# DCC-command-center-V2.net
KiCad netlist of a schematic drawn in EAGLE
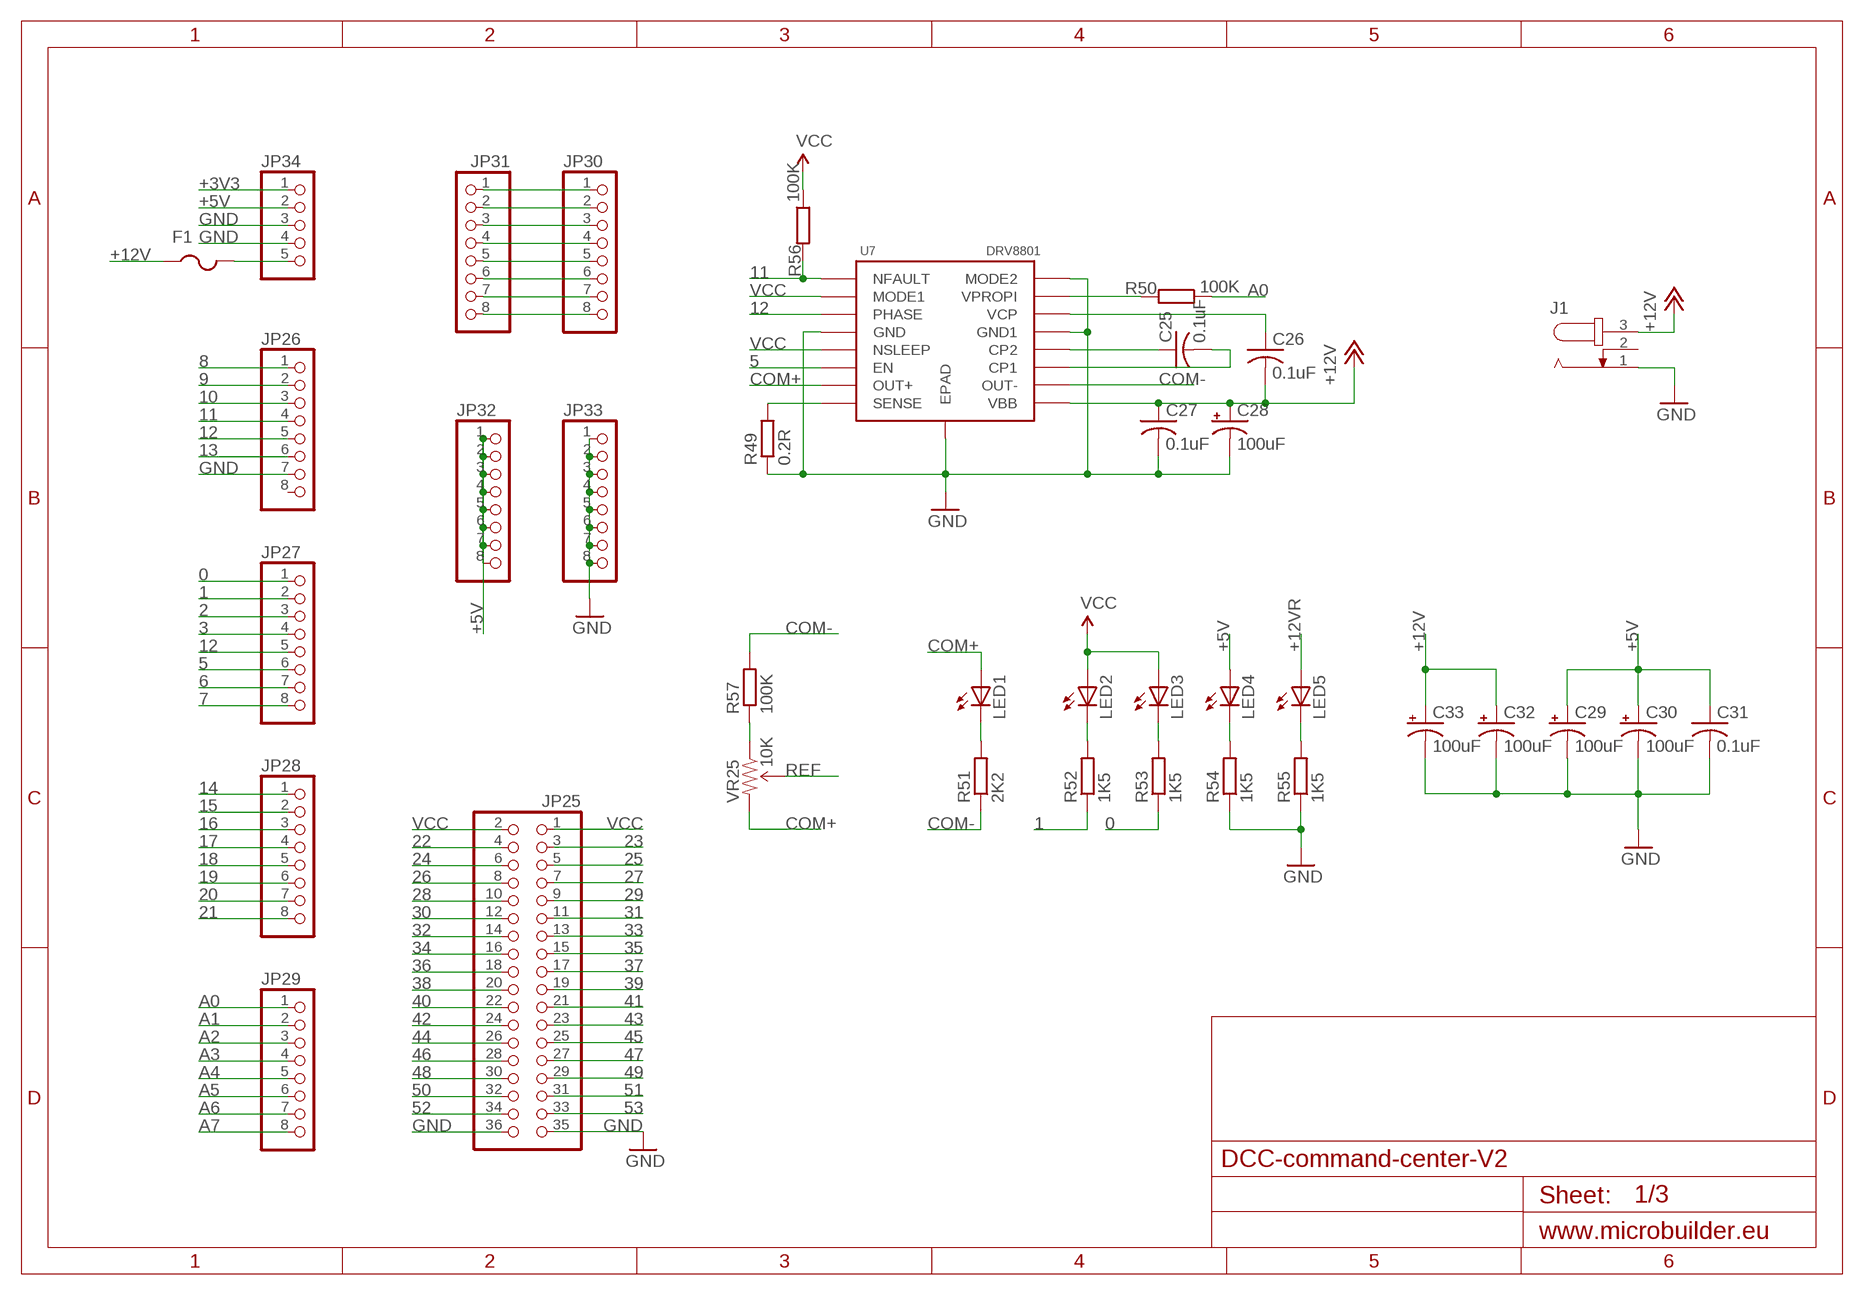
[diagram p0: schematic, sheet 1]
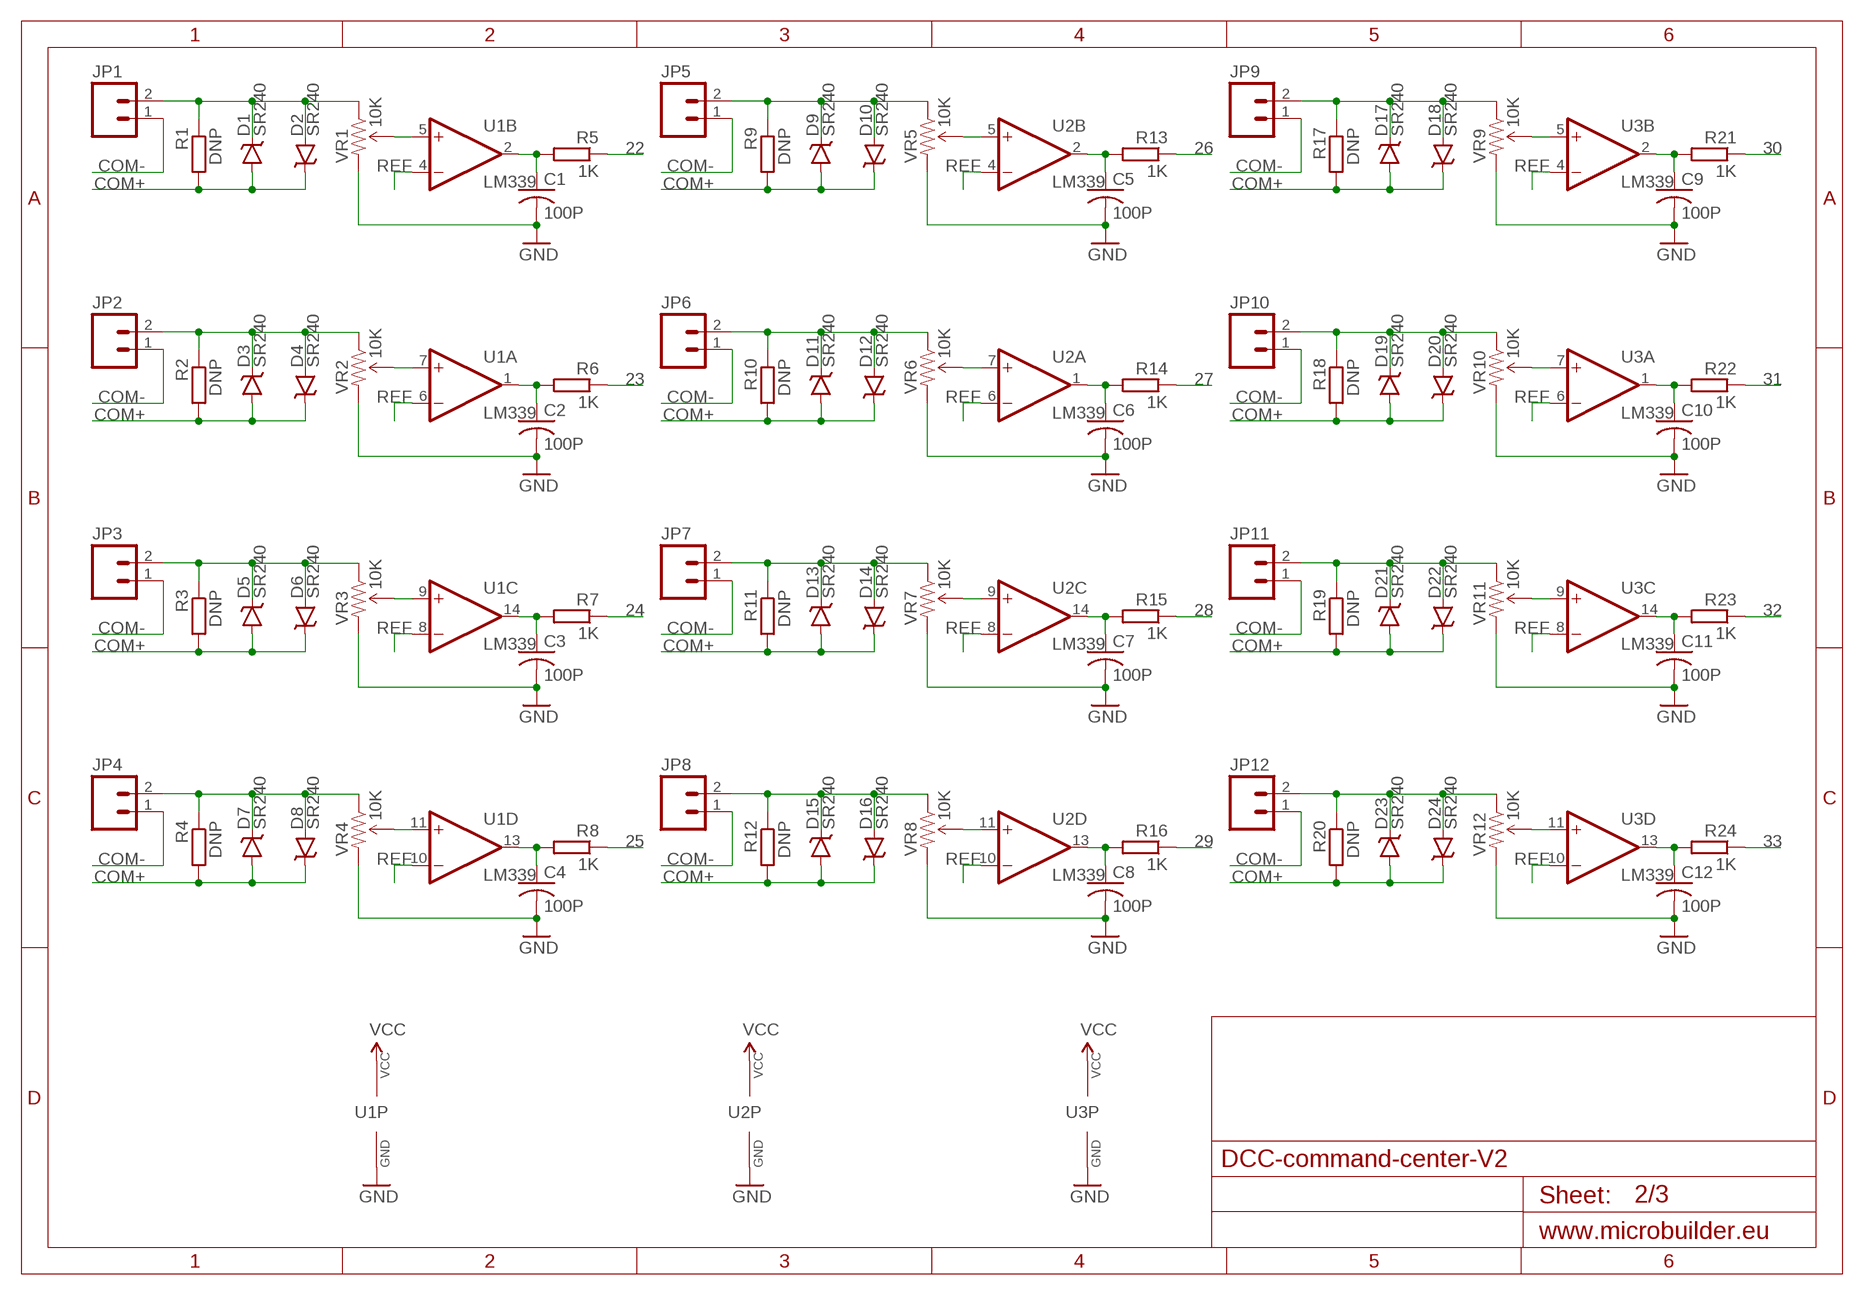
[diagram p1: schematic, sheet 2]
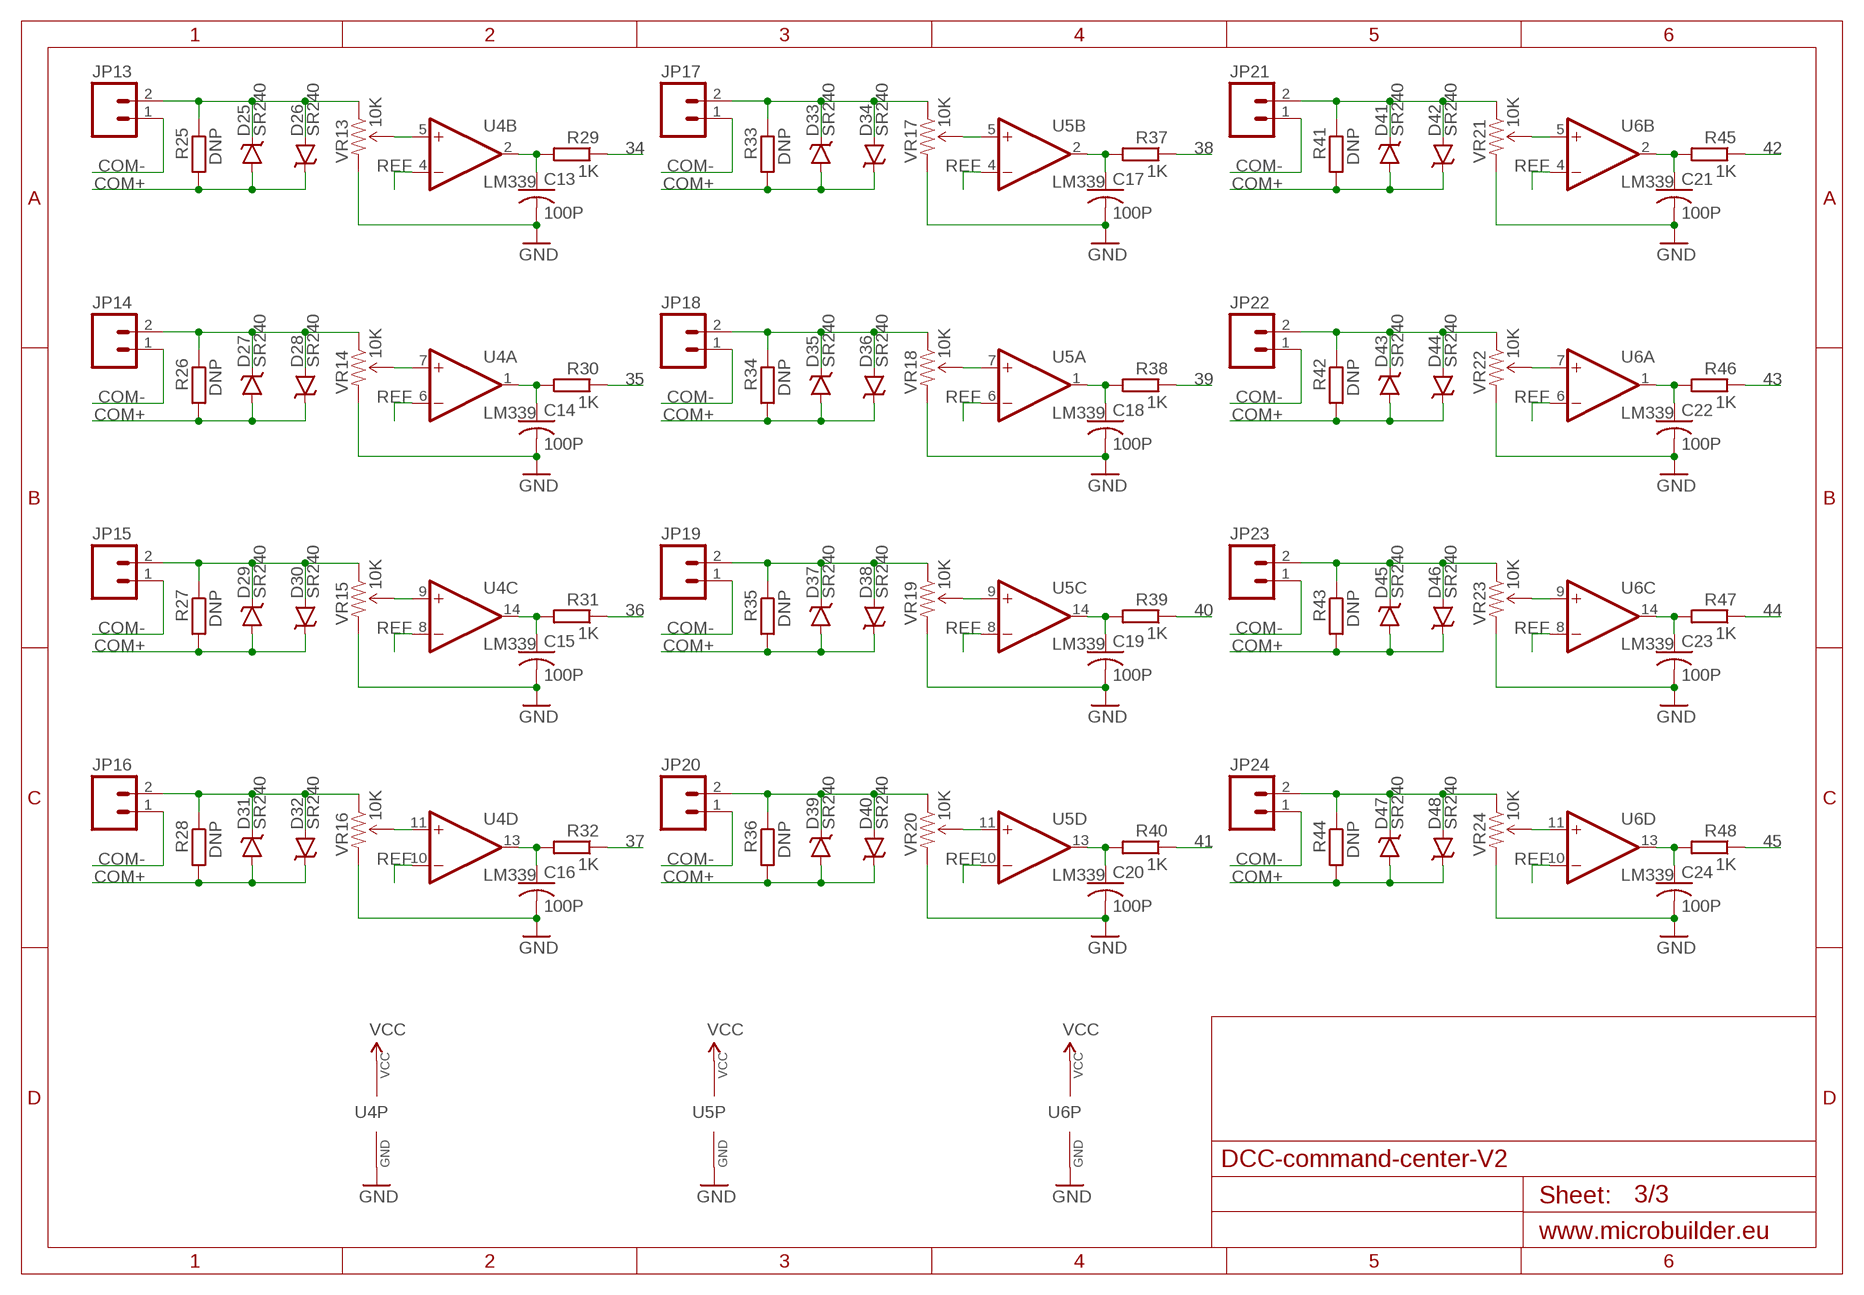
[diagram p2: schematic, sheet 3]

(export (version "E")
  (design (tool "Eeschema 10.0.6"))
  (components
    (comp (ref "C13")
      (value "100P")
      (footprint "eagle-import:C0603")
      (libsource (lib "eagle-import") (part "C-USC0603"))
    )
    (comp (ref "C14")
      (value "100P")
      (footprint "eagle-import:C0603")
      (libsource (lib "eagle-import") (part "C-USC0603"))
    )
    (comp (ref "C15")
      (value "100P")
      (footprint "eagle-import:C0603")
      (libsource (lib "eagle-import") (part "C-USC0603"))
    )
    (comp (ref "C16")
      (value "100P")
      (footprint "eagle-import:C0603")
      (libsource (lib "eagle-import") (part "C-USC0603"))
    )
    (comp (ref "C17")
      (value "100P")
      (footprint "eagle-import:C0603")
      (libsource (lib "eagle-import") (part "C-USC0603"))
    )
    (comp (ref "C18")
      (value "100P")
      (footprint "eagle-import:C0603")
      (libsource (lib "eagle-import") (part "C-USC0603"))
    )
    (comp (ref "C19")
      (value "100P")
      (footprint "eagle-import:C0603")
      (libsource (lib "eagle-import") (part "C-USC0603"))
    )
    (comp (ref "C20")
      (value "100P")
      (footprint "eagle-import:C0603")
      (libsource (lib "eagle-import") (part "C-USC0603"))
    )
    (comp (ref "C21")
      (value "100P")
      (footprint "eagle-import:C0603")
      (libsource (lib "eagle-import") (part "C-USC0603"))
    )
    (comp (ref "C22")
      (value "100P")
      (footprint "eagle-import:C0603")
      (libsource (lib "eagle-import") (part "C-USC0603"))
    )
    (comp (ref "C23")
      (value "100P")
      (footprint "eagle-import:C0603")
      (libsource (lib "eagle-import") (part "C-USC0603"))
    )
    (comp (ref "C24")
      (value "100P")
      (footprint "eagle-import:C0603")
      (libsource (lib "eagle-import") (part "C-USC0603"))
    )
    (comp (ref "D25")
      (value "SR240")
      (footprint "eagle-import:SMA-DIODE")
      (libsource (lib "eagle-import") (part "B340A"))
    )
    (comp (ref "D26")
      (value "SR240")
      (footprint "eagle-import:SMA-DIODE")
      (libsource (lib "eagle-import") (part "B340A"))
    )
    (comp (ref "D27")
      (value "SR240")
      (footprint "eagle-import:SMA-DIODE")
      (libsource (lib "eagle-import") (part "B340A"))
    )
    (comp (ref "D28")
      (value "SR240")
      (footprint "eagle-import:SMA-DIODE")
      (libsource (lib "eagle-import") (part "B340A"))
    )
    (comp (ref "D29")
      (value "SR240")
      (footprint "eagle-import:SMA-DIODE")
      (libsource (lib "eagle-import") (part "B340A"))
    )
    (comp (ref "D30")
      (value "SR240")
      (footprint "eagle-import:SMA-DIODE")
      (libsource (lib "eagle-import") (part "B340A"))
    )
    (comp (ref "D31")
      (value "SR240")
      (footprint "eagle-import:SMA-DIODE")
      (libsource (lib "eagle-import") (part "B340A"))
    )
    (comp (ref "D32")
      (value "SR240")
      (footprint "eagle-import:SMA-DIODE")
      (libsource (lib "eagle-import") (part "B340A"))
    )
    (comp (ref "D33")
      (value "SR240")
      (footprint "eagle-import:SMA-DIODE")
      (libsource (lib "eagle-import") (part "B340A"))
    )
    (comp (ref "D34")
      (value "SR240")
      (footprint "eagle-import:SMA-DIODE")
      (libsource (lib "eagle-import") (part "B340A"))
    )
    (comp (ref "D35")
      (value "SR240")
      (footprint "eagle-import:SMA-DIODE")
      (libsource (lib "eagle-import") (part "B340A"))
    )
    (comp (ref "D36")
      (value "SR240")
      (footprint "eagle-import:SMA-DIODE")
      (libsource (lib "eagle-import") (part "B340A"))
    )
    (comp (ref "D37")
      (value "SR240")
      (footprint "eagle-import:SMA-DIODE")
      (libsource (lib "eagle-import") (part "B340A"))
    )
    (comp (ref "D38")
      (value "SR240")
      (footprint "eagle-import:SMA-DIODE")
      (libsource (lib "eagle-import") (part "B340A"))
    )
    (comp (ref "D39")
      (value "SR240")
      (footprint "eagle-import:SMA-DIODE")
      (libsource (lib "eagle-import") (part "B340A"))
    )
    (comp (ref "D40")
      (value "SR240")
      (footprint "eagle-import:SMA-DIODE")
      (libsource (lib "eagle-import") (part "B340A"))
    )
    (comp (ref "D41")
      (value "SR240")
      (footprint "eagle-import:SMA-DIODE")
      (libsource (lib "eagle-import") (part "B340A"))
    )
    (comp (ref "D42")
      (value "SR240")
      (footprint "eagle-import:SMA-DIODE")
      (libsource (lib "eagle-import") (part "B340A"))
    )
    (comp (ref "D43")
      (value "SR240")
      (footprint "eagle-import:SMA-DIODE")
      (libsource (lib "eagle-import") (part "B340A"))
    )
    (comp (ref "D44")
      (value "SR240")
      (footprint "eagle-import:SMA-DIODE")
      (libsource (lib "eagle-import") (part "B340A"))
    )
    (comp (ref "D45")
      (value "SR240")
      (footprint "eagle-import:SMA-DIODE")
      (libsource (lib "eagle-import") (part "B340A"))
    )
    (comp (ref "D46")
      (value "SR240")
      (footprint "eagle-import:SMA-DIODE")
      (libsource (lib "eagle-import") (part "B340A"))
    )
    (comp (ref "D47")
      (value "SR240")
      (footprint "eagle-import:SMA-DIODE")
      (libsource (lib "eagle-import") (part "B340A"))
    )
    (comp (ref "D48")
      (value "SR240")
      (footprint "eagle-import:SMA-DIODE")
      (libsource (lib "eagle-import") (part "B340A"))
    )
    (comp (ref "JP13")
      (value "M02POGO_PIN_HOLES_ONLY")
      (footprint "eagle-import:1X02_PP_HOLES_ONLY")
      (libsource (lib "eagle-import") (part "M02POGO_PIN_HOLES_ONLY"))
    )
    (comp (ref "JP14")
      (value "M02POGO_PIN_HOLES_ONLY")
      (footprint "eagle-import:1X02_PP_HOLES_ONLY")
      (libsource (lib "eagle-import") (part "M02POGO_PIN_HOLES_ONLY"))
    )
    (comp (ref "JP15")
      (value "M02POGO_PIN_HOLES_ONLY")
      (footprint "eagle-import:1X02_PP_HOLES_ONLY")
      (libsource (lib "eagle-import") (part "M02POGO_PIN_HOLES_ONLY"))
    )
    (comp (ref "JP16")
      (value "M02POGO_PIN_HOLES_ONLY")
      (footprint "eagle-import:1X02_PP_HOLES_ONLY")
      (libsource (lib "eagle-import") (part "M02POGO_PIN_HOLES_ONLY"))
    )
    (comp (ref "JP17")
      (value "M02POGO_PIN_HOLES_ONLY")
      (footprint "eagle-import:1X02_PP_HOLES_ONLY")
      (libsource (lib "eagle-import") (part "M02POGO_PIN_HOLES_ONLY"))
    )
    (comp (ref "JP18")
      (value "M02POGO_PIN_HOLES_ONLY")
      (footprint "eagle-import:1X02_PP_HOLES_ONLY")
      (libsource (lib "eagle-import") (part "M02POGO_PIN_HOLES_ONLY"))
    )
    (comp (ref "JP19")
      (value "M02POGO_PIN_HOLES_ONLY")
      (footprint "eagle-import:1X02_PP_HOLES_ONLY")
      (libsource (lib "eagle-import") (part "M02POGO_PIN_HOLES_ONLY"))
    )
    (comp (ref "JP20")
      (value "M02POGO_PIN_HOLES_ONLY")
      (footprint "eagle-import:1X02_PP_HOLES_ONLY")
      (libsource (lib "eagle-import") (part "M02POGO_PIN_HOLES_ONLY"))
    )
    (comp (ref "JP21")
      (value "M02POGO_PIN_HOLES_ONLY")
      (footprint "eagle-import:1X02_PP_HOLES_ONLY")
      (libsource (lib "eagle-import") (part "M02POGO_PIN_HOLES_ONLY"))
    )
    (comp (ref "JP22")
      (value "M02POGO_PIN_HOLES_ONLY")
      (footprint "eagle-import:1X02_PP_HOLES_ONLY")
      (libsource (lib "eagle-import") (part "M02POGO_PIN_HOLES_ONLY"))
    )
    (comp (ref "JP23")
      (value "M02POGO_PIN_HOLES_ONLY")
      (footprint "eagle-import:1X02_PP_HOLES_ONLY")
      (libsource (lib "eagle-import") (part "M02POGO_PIN_HOLES_ONLY"))
    )
    (comp (ref "JP24")
      (value "M02POGO_PIN_HOLES_ONLY")
      (footprint "eagle-import:1X02_PP_HOLES_ONLY")
      (libsource (lib "eagle-import") (part "M02POGO_PIN_HOLES_ONLY"))
    )
    (comp (ref "R25")
      (value "DNP")
      (footprint "eagle-import:R0603")
      (libsource (lib "eagle-import") (part "R-EU_R0603"))
    )
    (comp (ref "R26")
      (value "DNP")
      (footprint "eagle-import:R0603")
      (libsource (lib "eagle-import") (part "R-EU_R0603"))
    )
    (comp (ref "R27")
      (value "DNP")
      (footprint "eagle-import:R0603")
      (libsource (lib "eagle-import") (part "R-EU_R0603"))
    )
    (comp (ref "R28")
      (value "DNP")
      (footprint "eagle-import:R0603")
      (libsource (lib "eagle-import") (part "R-EU_R0603"))
    )
    (comp (ref "R29")
      (value "1K")
      (footprint "eagle-import:R0603")
      (libsource (lib "eagle-import") (part "R-EU_R0603"))
    )
    (comp (ref "R30")
      (value "1K")
      (footprint "eagle-import:R0603")
      (libsource (lib "eagle-import") (part "R-EU_R0603"))
    )
    (comp (ref "R31")
      (value "1K")
      (footprint "eagle-import:R0603")
      (libsource (lib "eagle-import") (part "R-EU_R0603"))
    )
    (comp (ref "R32")
      (value "1K")
      (footprint "eagle-import:R0603")
      (libsource (lib "eagle-import") (part "R-EU_R0603"))
    )
    (comp (ref "R33")
      (value "DNP")
      (footprint "eagle-import:R0603")
      (libsource (lib "eagle-import") (part "R-EU_R0603"))
    )
    (comp (ref "R34")
      (value "DNP")
      (footprint "eagle-import:R0603")
      (libsource (lib "eagle-import") (part "R-EU_R0603"))
    )
    (comp (ref "R35")
      (value "DNP")
      (footprint "eagle-import:R0603")
      (libsource (lib "eagle-import") (part "R-EU_R0603"))
    )
    (comp (ref "R36")
      (value "DNP")
      (footprint "eagle-import:R0603")
      (libsource (lib "eagle-import") (part "R-EU_R0603"))
    )
    (comp (ref "R37")
      (value "1K")
      (footprint "eagle-import:R0603")
      (libsource (lib "eagle-import") (part "R-EU_R0603"))
    )
    (comp (ref "R38")
      (value "1K")
      (footprint "eagle-import:R0603")
      (libsource (lib "eagle-import") (part "R-EU_R0603"))
    )
    (comp (ref "R39")
      (value "1K")
      (footprint "eagle-import:R0603")
      (libsource (lib "eagle-import") (part "R-EU_R0603"))
    )
    (comp (ref "R40")
      (value "1K")
      (footprint "eagle-import:R0603")
      (libsource (lib "eagle-import") (part "R-EU_R0603"))
    )
    (comp (ref "R41")
      (value "DNP")
      (footprint "eagle-import:R0603")
      (libsource (lib "eagle-import") (part "R-EU_R0603"))
    )
    (comp (ref "R42")
      (value "DNP")
      (footprint "eagle-import:R0603")
      (libsource (lib "eagle-import") (part "R-EU_R0603"))
    )
    (comp (ref "R43")
      (value "DNP")
      (footprint "eagle-import:R0603")
      (libsource (lib "eagle-import") (part "R-EU_R0603"))
    )
    (comp (ref "R44")
      (value "DNP")
      (footprint "eagle-import:R0603")
      (libsource (lib "eagle-import") (part "R-EU_R0603"))
    )
    (comp (ref "R45")
      (value "1K")
      (footprint "eagle-import:R0603")
      (libsource (lib "eagle-import") (part "R-EU_R0603"))
    )
    (comp (ref "R46")
      (value "1K")
      (footprint "eagle-import:R0603")
      (libsource (lib "eagle-import") (part "R-EU_R0603"))
    )
    (comp (ref "R47")
      (value "1K")
      (footprint "eagle-import:R0603")
      (libsource (lib "eagle-import") (part "R-EU_R0603"))
    )
    (comp (ref "R48")
      (value "1K")
      (footprint "eagle-import:R0603")
      (libsource (lib "eagle-import") (part "R-EU_R0603"))
    )
    (comp (ref "U4")
      (value "LM339")
      (footprint "eagle-import:TSSOP-14")
      (fields (field (name "PARTNUM") "LM339PWR"))
      (libsource (lib "eagle-import") (part "LM339"))
    )
    (comp (ref "U5")
      (value "LM339")
      (footprint "eagle-import:TSSOP-14")
      (fields (field (name "PARTNUM") "LM339PWR"))
      (libsource (lib "eagle-import") (part "LM339"))
    )
    (comp (ref "U6")
      (value "LM339")
      (footprint "eagle-import:TSSOP-14")
      (fields (field (name "PARTNUM") "LM339PWR"))
      (libsource (lib "eagle-import") (part "LM339"))
    )
    (comp (ref "VR13")
      (value "10K")
      (footprint "eagle-import:TRIMPOT-3MM-2")
      (libsource (lib "eagle-import") (part "TRIMPOT3MM-2"))
    )
    (comp (ref "VR14")
      (value "10K")
      (footprint "eagle-import:TRIMPOT-3MM-2")
      (libsource (lib "eagle-import") (part "TRIMPOT3MM-2"))
    )
    (comp (ref "VR15")
      (value "10K")
      (footprint "eagle-import:TRIMPOT-3MM-2")
      (libsource (lib "eagle-import") (part "TRIMPOT3MM-2"))
    )
    (comp (ref "VR16")
      (value "10K")
      (footprint "eagle-import:TRIMPOT-3MM-2")
      (libsource (lib "eagle-import") (part "TRIMPOT3MM-2"))
    )
    (comp (ref "VR17")
      (value "10K")
      (footprint "eagle-import:TRIMPOT-3MM-2")
      (libsource (lib "eagle-import") (part "TRIMPOT3MM-2"))
    )
    (comp (ref "VR18")
      (value "10K")
      (footprint "eagle-import:TRIMPOT-3MM-2")
      (libsource (lib "eagle-import") (part "TRIMPOT3MM-2"))
    )
    (comp (ref "VR19")
      (value "10K")
      (footprint "eagle-import:TRIMPOT-3MM-2")
      (libsource (lib "eagle-import") (part "TRIMPOT3MM-2"))
    )
    (comp (ref "VR20")
      (value "10K")
      (footprint "eagle-import:TRIMPOT-3MM-2")
      (libsource (lib "eagle-import") (part "TRIMPOT3MM-2"))
    )
    (comp (ref "VR21")
      (value "10K")
      (footprint "eagle-import:TRIMPOT-3MM-2")
      (libsource (lib "eagle-import") (part "TRIMPOT3MM-2"))
    )
    (comp (ref "VR22")
      (value "10K")
      (footprint "eagle-import:TRIMPOT-3MM-2")
      (libsource (lib "eagle-import") (part "TRIMPOT3MM-2"))
    )
    (comp (ref "VR23")
      (value "10K")
      (footprint "eagle-import:TRIMPOT-3MM-2")
      (libsource (lib "eagle-import") (part "TRIMPOT3MM-2"))
    )
    (comp (ref "VR24")
      (value "10K")
      (footprint "eagle-import:TRIMPOT-3MM-2")
      (libsource (lib "eagle-import") (part "TRIMPOT3MM-2"))
    )
    (comp (ref "C25")
      (value "0.1uF")
      (footprint "eagle-import:C0603")
      (libsource (lib "eagle-import") (part "C-USC0603"))
    )
    (comp (ref "C26")
      (value "0.1uF")
      (footprint "eagle-import:C0603")
      (libsource (lib "eagle-import") (part "C-USC0603"))
    )
    (comp (ref "C27")
      (value "0.1uF")
      (footprint "eagle-import:C0603")
      (libsource (lib "eagle-import") (part "C-USC0603"))
    )
    (comp (ref "C28")
      (value "100uF")
      (footprint "eagle-import:153CLV-0505")
      (libsource (lib "eagle-import") (part "CPOL-US153CLV-0505"))
    )
    (comp (ref "C29")
      (value "100uF")
      (footprint "eagle-import:153CLV-0505")
      (libsource (lib "eagle-import") (part "CPOL-US153CLV-0505"))
    )
    (comp (ref "C30")
      (value "100uF")
      (footprint "eagle-import:153CLV-0505")
      (libsource (lib "eagle-import") (part "CPOL-US153CLV-0505"))
    )
    (comp (ref "C31")
      (value "0.1uF")
      (footprint "eagle-import:C0603")
      (libsource (lib "eagle-import") (part "C-USC0603"))
    )
    (comp (ref "C32")
      (value "100uF")
      (footprint "eagle-import:153CLV-0505")
      (libsource (lib "eagle-import") (part "CPOL-US153CLV-0505"))
    )
    (comp (ref "C33")
      (value "100uF")
      (footprint "eagle-import:153CLV-0505")
      (libsource (lib "eagle-import") (part "CPOL-US153CLV-0505"))
    )
    (comp (ref "F1")
      (value "PTCFUSE-1812")
      (footprint "eagle-import:1812")
      (libsource (lib "eagle-import") (part "PTCFUSE-1812"))
    )
    (comp (ref "J1")
      (value "RAPC7120")
      (footprint "eagle-import:RAPC712")
      (libsource (lib "eagle-import") (part "RAPC7120"))
    )
    (comp (ref "JP25")
      (value "PINHD-2X18_2.54")
      (footprint "eagle-import:2X18")
      (libsource (lib "eagle-import") (part "PINHD-2X18_2.54"))
    )
    (comp (ref "JP26")
      (value "PINHD-1X08_2.54-S")
      (footprint "eagle-import:1X08-S")
      (libsource (lib "eagle-import") (part "PINHD-1X08_2.54-S"))
    )
    (comp (ref "JP27")
      (value "PINHD-1X08_2.54-S")
      (footprint "eagle-import:1X08-S")
      (libsource (lib "eagle-import") (part "PINHD-1X08_2.54-S"))
    )
    (comp (ref "JP28")
      (value "PINHD-1X08_2.54-S")
      (footprint "eagle-import:1X08-S")
      (libsource (lib "eagle-import") (part "PINHD-1X08_2.54-S"))
    )
    (comp (ref "JP29")
      (value "PINHD-1X08_2.54-S")
      (footprint "eagle-import:1X08-S")
      (libsource (lib "eagle-import") (part "PINHD-1X08_2.54-S"))
    )
    (comp (ref "JP30")
      (value "PINHD-1X08_2.54-S")
      (footprint "eagle-import:1X08-S")
      (libsource (lib "eagle-import") (part "PINHD-1X08_2.54-S"))
    )
    (comp (ref "JP31")
      (value "PINHD-1X08_2.54-S")
      (footprint "eagle-import:1X08-S")
      (libsource (lib "eagle-import") (part "PINHD-1X08_2.54-S"))
    )
    (comp (ref "JP32")
      (value "PINHD-1X08_2.54-S")
      (footprint "eagle-import:1X08-S")
      (libsource (lib "eagle-import") (part "PINHD-1X08_2.54-S"))
    )
    (comp (ref "JP33")
      (value "PINHD-1X08_2.54-S")
      (footprint "eagle-import:1X08-S")
      (libsource (lib "eagle-import") (part "PINHD-1X08_2.54-S"))
    )
    (comp (ref "JP34")
      (value "PINHD-1X05_2.54-S")
      (footprint "eagle-import:1X05-S")
      (libsource (lib "eagle-import") (part "PINHD-1X05_2.54-S"))
    )
    (comp (ref "LED1")
      (value "LEDCHIP-LED0603")
      (footprint "eagle-import:CHIP-LED0603")
      (libsource (lib "eagle-import") (part "LEDCHIP-LED0603"))
    )
    (comp (ref "LED2")
      (value "LEDCHIP-LED0603")
      (footprint "eagle-import:CHIP-LED0603")
      (libsource (lib "eagle-import") (part "LEDCHIP-LED0603"))
    )
    (comp (ref "LED3")
      (value "LEDCHIP-LED0603")
      (footprint "eagle-import:CHIP-LED0603")
      (libsource (lib "eagle-import") (part "LEDCHIP-LED0603"))
    )
    (comp (ref "LED4")
      (value "LEDCHIP-LED0603")
      (footprint "eagle-import:CHIP-LED0603")
      (libsource (lib "eagle-import") (part "LEDCHIP-LED0603"))
    )
    (comp (ref "LED5")
      (value "LEDCHIP-LED0603")
      (footprint "eagle-import:CHIP-LED0603")
      (libsource (lib "eagle-import") (part "LEDCHIP-LED0603"))
    )
    (comp (ref "R49")
      (value "0.2R")
      (footprint "eagle-import:R2512")
      (libsource (lib "eagle-import") (part "R-EU_R2512"))
    )
    (comp (ref "R50")
      (value "100K")
      (footprint "eagle-import:R0603")
      (libsource (lib "eagle-import") (part "R-EU_R0603"))
    )
    (comp (ref "R51")
      (value "2K2")
      (footprint "eagle-import:R0603")
      (libsource (lib "eagle-import") (part "R-EU_R0603"))
    )
    (comp (ref "R52")
      (value "1K5")
      (footprint "eagle-import:R0603")
      (libsource (lib "eagle-import") (part "R-EU_R0603"))
    )
    (comp (ref "R53")
      (value "1K5")
      (footprint "eagle-import:R0603")
      (libsource (lib "eagle-import") (part "R-EU_R0603"))
    )
    (comp (ref "R54")
      (value "1K5")
      (footprint "eagle-import:R0603")
      (libsource (lib "eagle-import") (part "R-EU_R0603"))
    )
    (comp (ref "R55")
      (value "1K5")
      (footprint "eagle-import:R0603")
      (libsource (lib "eagle-import") (part "R-EU_R0603"))
    )
    (comp (ref "R56")
      (value "100K")
      (footprint "eagle-import:R0603")
      (libsource (lib "eagle-import") (part "R-EU_R0603"))
    )
    (comp (ref "R57")
      (value "100K")
      (footprint "eagle-import:R0603")
      (libsource (lib "eagle-import") (part "R-EU_R0603"))
    )
    (comp (ref "U7")
      (value "DRV8801")
      (footprint "eagle-import:HTSSOP16")
      (libsource (lib "eagle-import") (part "DRV8801"))
    )
    (comp (ref "VR25")
      (value "10K")
      (footprint "eagle-import:TRIMPOT-3MM-2")
      (libsource (lib "eagle-import") (part "TRIMPOT3MM-2"))
    )
    (comp (ref "C1")
      (value "100P")
      (footprint "eagle-import:C0603")
      (libsource (lib "eagle-import") (part "C-USC0603"))
    )
    (comp (ref "C2")
      (value "100P")
      (footprint "eagle-import:C0603")
      (libsource (lib "eagle-import") (part "C-USC0603"))
    )
    (comp (ref "C3")
      (value "100P")
      (footprint "eagle-import:C0603")
      (libsource (lib "eagle-import") (part "C-USC0603"))
    )
    (comp (ref "C4")
      (value "100P")
      (footprint "eagle-import:C0603")
      (libsource (lib "eagle-import") (part "C-USC0603"))
    )
    (comp (ref "C5")
      (value "100P")
      (footprint "eagle-import:C0603")
      (libsource (lib "eagle-import") (part "C-USC0603"))
    )
    (comp (ref "C6")
      (value "100P")
      (footprint "eagle-import:C0603")
      (libsource (lib "eagle-import") (part "C-USC0603"))
    )
    (comp (ref "C7")
      (value "100P")
      (footprint "eagle-import:C0603")
      (libsource (lib "eagle-import") (part "C-USC0603"))
    )
    (comp (ref "C8")
      (value "100P")
      (footprint "eagle-import:C0603")
      (libsource (lib "eagle-import") (part "C-USC0603"))
    )
    (comp (ref "C9")
      (value "100P")
      (footprint "eagle-import:C0603")
      (libsource (lib "eagle-import") (part "C-USC0603"))
    )
    (comp (ref "C10")
      (value "100P")
      (footprint "eagle-import:C0603")
      (libsource (lib "eagle-import") (part "C-USC0603"))
    )
    (comp (ref "C11")
      (value "100P")
      (footprint "eagle-import:C0603")
      (libsource (lib "eagle-import") (part "C-USC0603"))
    )
    (comp (ref "C12")
      (value "100P")
      (footprint "eagle-import:C0603")
      (libsource (lib "eagle-import") (part "C-USC0603"))
    )
    (comp (ref "D1")
      (value "SR240")
      (footprint "eagle-import:SMA-DIODE")
      (libsource (lib "eagle-import") (part "B340A"))
    )
    (comp (ref "D2")
      (value "SR240")
      (footprint "eagle-import:SMA-DIODE")
      (libsource (lib "eagle-import") (part "B340A"))
    )
    (comp (ref "D3")
      (value "SR240")
      (footprint "eagle-import:SMA-DIODE")
      (libsource (lib "eagle-import") (part "B340A"))
    )
    (comp (ref "D4")
      (value "SR240")
      (footprint "eagle-import:SMA-DIODE")
      (libsource (lib "eagle-import") (part "B340A"))
    )
    (comp (ref "D5")
      (value "SR240")
      (footprint "eagle-import:SMA-DIODE")
      (libsource (lib "eagle-import") (part "B340A"))
    )
    (comp (ref "D6")
      (value "SR240")
      (footprint "eagle-import:SMA-DIODE")
      (libsource (lib "eagle-import") (part "B340A"))
    )
    (comp (ref "D7")
      (value "SR240")
      (footprint "eagle-import:SMA-DIODE")
      (libsource (lib "eagle-import") (part "B340A"))
    )
    (comp (ref "D8")
      (value "SR240")
      (footprint "eagle-import:SMA-DIODE")
      (libsource (lib "eagle-import") (part "B340A"))
    )
    (comp (ref "D9")
      (value "SR240")
      (footprint "eagle-import:SMA-DIODE")
      (libsource (lib "eagle-import") (part "B340A"))
    )
    (comp (ref "D10")
      (value "SR240")
      (footprint "eagle-import:SMA-DIODE")
      (libsource (lib "eagle-import") (part "B340A"))
    )
    (comp (ref "D11")
      (value "SR240")
      (footprint "eagle-import:SMA-DIODE")
      (libsource (lib "eagle-import") (part "B340A"))
    )
    (comp (ref "D12")
      (value "SR240")
      (footprint "eagle-import:SMA-DIODE")
      (libsource (lib "eagle-import") (part "B340A"))
    )
    (comp (ref "D13")
      (value "SR240")
      (footprint "eagle-import:SMA-DIODE")
      (libsource (lib "eagle-import") (part "B340A"))
    )
    (comp (ref "D14")
      (value "SR240")
      (footprint "eagle-import:SMA-DIODE")
      (libsource (lib "eagle-import") (part "B340A"))
    )
    (comp (ref "D15")
      (value "SR240")
      (footprint "eagle-import:SMA-DIODE")
      (libsource (lib "eagle-import") (part "B340A"))
    )
    (comp (ref "D16")
      (value "SR240")
      (footprint "eagle-import:SMA-DIODE")
      (libsource (lib "eagle-import") (part "B340A"))
    )
    (comp (ref "D17")
      (value "SR240")
      (footprint "eagle-import:SMA-DIODE")
      (libsource (lib "eagle-import") (part "B340A"))
    )
    (comp (ref "D18")
      (value "SR240")
      (footprint "eagle-import:SMA-DIODE")
      (libsource (lib "eagle-import") (part "B340A"))
    )
    (comp (ref "D19")
      (value "SR240")
      (footprint "eagle-import:SMA-DIODE")
      (libsource (lib "eagle-import") (part "B340A"))
    )
    (comp (ref "D20")
      (value "SR240")
      (footprint "eagle-import:SMA-DIODE")
      (libsource (lib "eagle-import") (part "B340A"))
    )
    (comp (ref "D21")
      (value "SR240")
      (footprint "eagle-import:SMA-DIODE")
      (libsource (lib "eagle-import") (part "B340A"))
    )
    (comp (ref "D22")
      (value "SR240")
      (footprint "eagle-import:SMA-DIODE")
      (libsource (lib "eagle-import") (part "B340A"))
    )
    (comp (ref "D23")
      (value "SR240")
      (footprint "eagle-import:SMA-DIODE")
      (libsource (lib "eagle-import") (part "B340A"))
    )
    (comp (ref "D24")
      (value "SR240")
      (footprint "eagle-import:SMA-DIODE")
      (libsource (lib "eagle-import") (part "B340A"))
    )
    (comp (ref "JP1")
      (value "M02POGO_PIN_HOLES_ONLY")
      (footprint "eagle-import:1X02_PP_HOLES_ONLY")
      (libsource (lib "eagle-import") (part "M02POGO_PIN_HOLES_ONLY"))
    )
    (comp (ref "JP2")
      (value "M02POGO_PIN_HOLES_ONLY")
      (footprint "eagle-import:1X02_PP_HOLES_ONLY")
      (libsource (lib "eagle-import") (part "M02POGO_PIN_HOLES_ONLY"))
    )
    (comp (ref "JP3")
      (value "M02POGO_PIN_HOLES_ONLY")
      (footprint "eagle-import:1X02_PP_HOLES_ONLY")
      (libsource (lib "eagle-import") (part "M02POGO_PIN_HOLES_ONLY"))
    )
    (comp (ref "JP4")
      (value "M02POGO_PIN_HOLES_ONLY")
      (footprint "eagle-import:1X02_PP_HOLES_ONLY")
      (libsource (lib "eagle-import") (part "M02POGO_PIN_HOLES_ONLY"))
    )
    (comp (ref "JP5")
      (value "M02POGO_PIN_HOLES_ONLY")
      (footprint "eagle-import:1X02_PP_HOLES_ONLY")
      (libsource (lib "eagle-import") (part "M02POGO_PIN_HOLES_ONLY"))
    )
    (comp (ref "JP6")
      (value "M02POGO_PIN_HOLES_ONLY")
      (footprint "eagle-import:1X02_PP_HOLES_ONLY")
      (libsource (lib "eagle-import") (part "M02POGO_PIN_HOLES_ONLY"))
    )
    (comp (ref "JP7")
      (value "M02POGO_PIN_HOLES_ONLY")
      (footprint "eagle-import:1X02_PP_HOLES_ONLY")
      (libsource (lib "eagle-import") (part "M02POGO_PIN_HOLES_ONLY"))
    )
    (comp (ref "JP8")
      (value "M02POGO_PIN_HOLES_ONLY")
      (footprint "eagle-import:1X02_PP_HOLES_ONLY")
      (libsource (lib "eagle-import") (part "M02POGO_PIN_HOLES_ONLY"))
    )
    (comp (ref "JP9")
      (value "M02POGO_PIN_HOLES_ONLY")
      (footprint "eagle-import:1X02_PP_HOLES_ONLY")
      (libsource (lib "eagle-import") (part "M02POGO_PIN_HOLES_ONLY"))
    )
    (comp (ref "JP10")
      (value "M02POGO_PIN_HOLES_ONLY")
      (footprint "eagle-import:1X02_PP_HOLES_ONLY")
      (libsource (lib "eagle-import") (part "M02POGO_PIN_HOLES_ONLY"))
    )
    (comp (ref "JP11")
      (value "M02POGO_PIN_HOLES_ONLY")
      (footprint "eagle-import:1X02_PP_HOLES_ONLY")
      (libsource (lib "eagle-import") (part "M02POGO_PIN_HOLES_ONLY"))
    )
    (comp (ref "JP12")
      (value "M02POGO_PIN_HOLES_ONLY")
      (footprint "eagle-import:1X02_PP_HOLES_ONLY")
      (libsource (lib "eagle-import") (part "M02POGO_PIN_HOLES_ONLY"))
    )
    (comp (ref "R1")
      (value "DNP")
      (footprint "eagle-import:R0603")
      (libsource (lib "eagle-import") (part "R-EU_R0603"))
    )
    (comp (ref "R2")
      (value "DNP")
      (footprint "eagle-import:R0603")
      (libsource (lib "eagle-import") (part "R-EU_R0603"))
    )
    (comp (ref "R3")
      (value "DNP")
      (footprint "eagle-import:R0603")
      (libsource (lib "eagle-import") (part "R-EU_R0603"))
    )
    (comp (ref "R4")
      (value "DNP")
      (footprint "eagle-import:R0603")
      (libsource (lib "eagle-import") (part "R-EU_R0603"))
    )
    (comp (ref "R5")
      (value "1K")
      (footprint "eagle-import:R0603")
      (libsource (lib "eagle-import") (part "R-EU_R0603"))
    )
    (comp (ref "R6")
      (value "1K")
      (footprint "eagle-import:R0603")
      (libsource (lib "eagle-import") (part "R-EU_R0603"))
    )
    (comp (ref "R7")
      (value "1K")
      (footprint "eagle-import:R0603")
      (libsource (lib "eagle-import") (part "R-EU_R0603"))
    )
    (comp (ref "R8")
      (value "1K")
      (footprint "eagle-import:R0603")
      (libsource (lib "eagle-import") (part "R-EU_R0603"))
    )
    (comp (ref "R9")
      (value "DNP")
      (footprint "eagle-import:R0603")
      (libsource (lib "eagle-import") (part "R-EU_R0603"))
    )
    (comp (ref "R10")
      (value "DNP")
      (footprint "eagle-import:R0603")
      (libsource (lib "eagle-import") (part "R-EU_R0603"))
    )
    (comp (ref "R11")
      (value "DNP")
      (footprint "eagle-import:R0603")
      (libsource (lib "eagle-import") (part "R-EU_R0603"))
    )
    (comp (ref "R12")
      (value "DNP")
      (footprint "eagle-import:R0603")
      (libsource (lib "eagle-import") (part "R-EU_R0603"))
    )
    (comp (ref "R13")
      (value "1K")
      (footprint "eagle-import:R0603")
      (libsource (lib "eagle-import") (part "R-EU_R0603"))
    )
    (comp (ref "R14")
      (value "1K")
      (footprint "eagle-import:R0603")
      (libsource (lib "eagle-import") (part "R-EU_R0603"))
    )
    (comp (ref "R15")
      (value "1K")
      (footprint "eagle-import:R0603")
      (libsource (lib "eagle-import") (part "R-EU_R0603"))
    )
    (comp (ref "R16")
      (value "1K")
      (footprint "eagle-import:R0603")
      (libsource (lib "eagle-import") (part "R-EU_R0603"))
    )
    (comp (ref "R17")
      (value "DNP")
      (footprint "eagle-import:R0603")
      (libsource (lib "eagle-import") (part "R-EU_R0603"))
    )
    (comp (ref "R18")
      (value "DNP")
      (footprint "eagle-import:R0603")
      (libsource (lib "eagle-import") (part "R-EU_R0603"))
    )
    (comp (ref "R19")
      (value "DNP")
      (footprint "eagle-import:R0603")
      (libsource (lib "eagle-import") (part "R-EU_R0603"))
    )
    (comp (ref "R20")
      (value "DNP")
      (footprint "eagle-import:R0603")
      (libsource (lib "eagle-import") (part "R-EU_R0603"))
    )
    (comp (ref "R21")
      (value "1K")
      (footprint "eagle-import:R0603")
      (libsource (lib "eagle-import") (part "R-EU_R0603"))
    )
    (comp (ref "R22")
      (value "1K")
      (footprint "eagle-import:R0603")
      (libsource (lib "eagle-import") (part "R-EU_R0603"))
    )
    (comp (ref "R23")
      (value "1K")
      (footprint "eagle-import:R0603")
      (libsource (lib "eagle-import") (part "R-EU_R0603"))
    )
    (comp (ref "R24")
      (value "1K")
      (footprint "eagle-import:R0603")
      (libsource (lib "eagle-import") (part "R-EU_R0603"))
    )
    (comp (ref "U1")
      (value "LM339")
      (footprint "eagle-import:TSSOP-14")
      (fields (field (name "PARTNUM") "LM339PWR"))
      (libsource (lib "eagle-import") (part "LM339"))
    )
    (comp (ref "U2")
      (value "LM339")
      (footprint "eagle-import:TSSOP-14")
      (fields (field (name "PARTNUM") "LM339PWR"))
      (libsource (lib "eagle-import") (part "LM339"))
    )
    (comp (ref "U3")
      (value "LM339")
      (footprint "eagle-import:TSSOP-14")
      (fields (field (name "PARTNUM") "LM339PWR"))
      (libsource (lib "eagle-import") (part "LM339"))
    )
    (comp (ref "VR1")
      (value "10K")
      (footprint "eagle-import:TRIMPOT-3MM-2")
      (libsource (lib "eagle-import") (part "TRIMPOT3MM-2"))
    )
    (comp (ref "VR2")
      (value "10K")
      (footprint "eagle-import:TRIMPOT-3MM-2")
      (libsource (lib "eagle-import") (part "TRIMPOT3MM-2"))
    )
    (comp (ref "VR3")
      (value "10K")
      (footprint "eagle-import:TRIMPOT-3MM-2")
      (libsource (lib "eagle-import") (part "TRIMPOT3MM-2"))
    )
    (comp (ref "VR4")
      (value "10K")
      (footprint "eagle-import:TRIMPOT-3MM-2")
      (libsource (lib "eagle-import") (part "TRIMPOT3MM-2"))
    )
    (comp (ref "VR5")
      (value "10K")
      (footprint "eagle-import:TRIMPOT-3MM-2")
      (libsource (lib "eagle-import") (part "TRIMPOT3MM-2"))
    )
    (comp (ref "VR6")
      (value "10K")
      (footprint "eagle-import:TRIMPOT-3MM-2")
      (libsource (lib "eagle-import") (part "TRIMPOT3MM-2"))
    )
    (comp (ref "VR7")
      (value "10K")
      (footprint "eagle-import:TRIMPOT-3MM-2")
      (libsource (lib "eagle-import") (part "TRIMPOT3MM-2"))
    )
    (comp (ref "VR8")
      (value "10K")
      (footprint "eagle-import:TRIMPOT-3MM-2")
      (libsource (lib "eagle-import") (part "TRIMPOT3MM-2"))
    )
    (comp (ref "VR9")
      (value "10K")
      (footprint "eagle-import:TRIMPOT-3MM-2")
      (libsource (lib "eagle-import") (part "TRIMPOT3MM-2"))
    )
    (comp (ref "VR10")
      (value "10K")
      (footprint "eagle-import:TRIMPOT-3MM-2")
      (libsource (lib "eagle-import") (part "TRIMPOT3MM-2"))
    )
    (comp (ref "VR11")
      (value "10K")
      (footprint "eagle-import:TRIMPOT-3MM-2")
      (libsource (lib "eagle-import") (part "TRIMPOT3MM-2"))
    )
    (comp (ref "VR12")
      (value "10K")
      (footprint "eagle-import:TRIMPOT-3MM-2")
      (libsource (lib "eagle-import") (part "TRIMPOT3MM-2"))
    )
  )
  (nets
    (net (code "1") (name "+3V3") (class "Default")
      (node (ref "JP34") (pin "1") (pinfunction "1_1") (pintype "passive"))
    )
    (net (code "2") (name "+5V") (class "Default")
      (node (ref "C29") (pin "+") (pinfunction "+_+") (pintype "passive"))
      (node (ref "C30") (pin "+") (pinfunction "+_+") (pintype "passive"))
      (node (ref "C31") (pin "1") (pinfunction "1_1") (pintype "passive"))
      (node (ref "JP32") (pin "1") (pinfunction "1_1") (pintype "passive"))
      (node (ref "JP32") (pin "2") (pinfunction "2_2") (pintype "passive"))
      (node (ref "JP32") (pin "3") (pinfunction "3_3") (pintype "passive"))
      (node (ref "JP32") (pin "4") (pinfunction "4_4") (pintype "passive"))
      (node (ref "JP32") (pin "5") (pinfunction "5_5") (pintype "passive"))
      (node (ref "JP32") (pin "6") (pinfunction "6_6") (pintype "passive"))
      (node (ref "JP32") (pin "7") (pinfunction "7_7") (pintype "passive"))
      (node (ref "JP32") (pin "8") (pinfunction "8_8") (pintype "passive"))
      (node (ref "JP34") (pin "2") (pinfunction "2_2") (pintype "passive"))
      (node (ref "LED4") (pin "A") (pinfunction "A_A") (pintype "passive"))
    )
    (net (code "3") (name "+12V") (class "Default")
      (node (ref "C26") (pin "2") (pinfunction "2_2") (pintype "passive"))
      (node (ref "C27") (pin "1") (pinfunction "1_1") (pintype "passive"))
      (node (ref "C28") (pin "+") (pinfunction "+_+") (pintype "passive"))
      (node (ref "C32") (pin "+") (pinfunction "+_+") (pintype "passive"))
      (node (ref "C33") (pin "+") (pinfunction "+_+") (pintype "passive"))
      (node (ref "F1") (pin "1") (pinfunction "1_1") (pintype "passive"))
      (node (ref "J1") (pin "3") (pinfunction "3_3") (pintype "passive"))
      (node (ref "U7") (pin "P$9") (pinfunction "VBB_P$9") (pintype "bidirectional"))
    )
    (net (code "4") (name "+12VR") (class "Default")
      (node (ref "F1") (pin "2") (pinfunction "2_2") (pintype "passive"))
      (node (ref "JP34") (pin "5") (pinfunction "5_5") (pintype "passive"))
      (node (ref "LED5") (pin "A") (pinfunction "A_A") (pintype "passive"))
    )
    (net (code "5") (name "0") (class "Default")
      (node (ref "JP27") (pin "1") (pinfunction "1_1") (pintype "passive"))
      (node (ref "R53") (pin "1") (pinfunction "1_1") (pintype "passive"))
    )
    (net (code "6") (name "1") (class "Default")
      (node (ref "JP27") (pin "2") (pinfunction "2_2") (pintype "passive"))
      (node (ref "R52") (pin "1") (pinfunction "1_1") (pintype "passive"))
    )
    (net (code "7") (name "2") (class "Default")
      (node (ref "JP27") (pin "3") (pinfunction "3_3") (pintype "passive"))
    )
    (net (code "8") (name "3") (class "Default")
      (node (ref "JP27") (pin "4") (pinfunction "4_4") (pintype "passive"))
    )
    (net (code "9") (name "5") (class "Default")
      (node (ref "JP27") (pin "6") (pinfunction "6_6") (pintype "passive"))
      (node (ref "U7") (pin "P$6") (pinfunction "EN_P$6") (pintype "bidirectional"))
    )
    (net (code "10") (name "6") (class "Default")
      (node (ref "JP27") (pin "7") (pinfunction "7_7") (pintype "passive"))
    )
    (net (code "11") (name "7") (class "Default")
      (node (ref "JP27") (pin "8") (pinfunction "8_8") (pintype "passive"))
    )
    (net (code "12") (name "8") (class "Default")
      (node (ref "JP26") (pin "1") (pinfunction "1_1") (pintype "passive"))
    )
    (net (code "13") (name "9") (class "Default")
      (node (ref "JP26") (pin "2") (pinfunction "2_2") (pintype "passive"))
    )
    (net (code "14") (name "10") (class "Default")
      (node (ref "JP26") (pin "3") (pinfunction "3_3") (pintype "passive"))
    )
    (net (code "15") (name "11") (class "Default")
      (node (ref "JP26") (pin "4") (pinfunction "4_4") (pintype "passive"))
      (node (ref "R56") (pin "2") (pinfunction "2_2") (pintype "passive"))
      (node (ref "U7") (pin "P$1") (pinfunction "NFAULT_P$1") (pintype "bidirectional"))
    )
    (net (code "16") (name "12") (class "Default")
      (node (ref "JP26") (pin "5") (pinfunction "5_5") (pintype "passive"))
      (node (ref "JP27") (pin "5") (pinfunction "5_5") (pintype "passive"))
      (node (ref "U7") (pin "P$3") (pinfunction "PHASE_P$3") (pintype "bidirectional"))
    )
    (net (code "17") (name "13") (class "Default")
      (node (ref "JP26") (pin "6") (pinfunction "6_6") (pintype "passive"))
    )
    (net (code "18") (name "14") (class "Default")
      (node (ref "JP28") (pin "1") (pinfunction "1_1") (pintype "passive"))
    )
    (net (code "19") (name "15") (class "Default")
      (node (ref "JP28") (pin "2") (pinfunction "2_2") (pintype "passive"))
    )
    (net (code "20") (name "16") (class "Default")
      (node (ref "JP28") (pin "3") (pinfunction "3_3") (pintype "passive"))
    )
    (net (code "21") (name "17") (class "Default")
      (node (ref "JP28") (pin "4") (pinfunction "4_4") (pintype "passive"))
    )
    (net (code "22") (name "18") (class "Default")
      (node (ref "JP28") (pin "5") (pinfunction "5_5") (pintype "passive"))
    )
    (net (code "23") (name "19") (class "Default")
      (node (ref "JP28") (pin "6") (pinfunction "6_6") (pintype "passive"))
    )
    (net (code "24") (name "20") (class "Default")
      (node (ref "JP28") (pin "7") (pinfunction "7_7") (pintype "passive"))
    )
    (net (code "25") (name "21") (class "Default")
      (node (ref "JP28") (pin "8") (pinfunction "8_8") (pintype "passive"))
    )
    (net (code "26") (name "22") (class "Default")
      (node (ref "JP25") (pin "4") (pinfunction "4_4") (pintype "passive"))
      (node (ref "R5") (pin "1") (pinfunction "1_1") (pintype "passive"))
    )
    (net (code "27") (name "23") (class "Default")
      (node (ref "JP25") (pin "3") (pinfunction "3_3") (pintype "passive"))
      (node (ref "R6") (pin "1") (pinfunction "1_1") (pintype "passive"))
    )
    (net (code "28") (name "24") (class "Default")
      (node (ref "JP25") (pin "6") (pinfunction "6_6") (pintype "passive"))
      (node (ref "R7") (pin "1") (pinfunction "1_1") (pintype "passive"))
    )
    (net (code "29") (name "25") (class "Default")
      (node (ref "JP25") (pin "5") (pinfunction "5_5") (pintype "passive"))
      (node (ref "R8") (pin "1") (pinfunction "1_1") (pintype "passive"))
    )
    (net (code "30") (name "26") (class "Default")
      (node (ref "JP25") (pin "8") (pinfunction "8_8") (pintype "passive"))
      (node (ref "R13") (pin "1") (pinfunction "1_1") (pintype "passive"))
    )
    (net (code "31") (name "27") (class "Default")
      (node (ref "JP25") (pin "7") (pinfunction "7_7") (pintype "passive"))
      (node (ref "R14") (pin "1") (pinfunction "1_1") (pintype "passive"))
    )
    (net (code "32") (name "28") (class "Default")
      (node (ref "JP25") (pin "10") (pinfunction "10_10") (pintype "passive"))
      (node (ref "R15") (pin "1") (pinfunction "1_1") (pintype "passive"))
    )
    (net (code "33") (name "29") (class "Default")
      (node (ref "JP25") (pin "9") (pinfunction "9_9") (pintype "passive"))
      (node (ref "R16") (pin "1") (pinfunction "1_1") (pintype "passive"))
    )
    (net (code "34") (name "30") (class "Default")
      (node (ref "JP25") (pin "12") (pinfunction "12_12") (pintype "passive"))
      (node (ref "R21") (pin "1") (pinfunction "1_1") (pintype "passive"))
    )
    (net (code "35") (name "31") (class "Default")
      (node (ref "JP25") (pin "11") (pinfunction "11_11") (pintype "passive"))
      (node (ref "R22") (pin "1") (pinfunction "1_1") (pintype "passive"))
    )
    (net (code "36") (name "32") (class "Default")
      (node (ref "JP25") (pin "14") (pinfunction "14_14") (pintype "passive"))
      (node (ref "R23") (pin "1") (pinfunction "1_1") (pintype "passive"))
    )
    (net (code "37") (name "33") (class "Default")
      (node (ref "JP25") (pin "13") (pinfunction "13_13") (pintype "passive"))
      (node (ref "R24") (pin "1") (pinfunction "1_1") (pintype "passive"))
    )
    (net (code "38") (name "34") (class "Default")
      (node (ref "JP25") (pin "16") (pinfunction "16_16") (pintype "passive"))
      (node (ref "R29") (pin "1") (pinfunction "1_1") (pintype "passive"))
    )
    (net (code "39") (name "35") (class "Default")
      (node (ref "JP25") (pin "15") (pinfunction "15_15") (pintype "passive"))
      (node (ref "R30") (pin "1") (pinfunction "1_1") (pintype "passive"))
    )
    (net (code "40") (name "36") (class "Default")
      (node (ref "JP25") (pin "18") (pinfunction "18_18") (pintype "passive"))
      (node (ref "R31") (pin "1") (pinfunction "1_1") (pintype "passive"))
    )
    (net (code "41") (name "37") (class "Default")
      (node (ref "JP25") (pin "17") (pinfunction "17_17") (pintype "passive"))
      (node (ref "R32") (pin "1") (pinfunction "1_1") (pintype "passive"))
    )
    (net (code "42") (name "38") (class "Default")
      (node (ref "JP25") (pin "20") (pinfunction "20_20") (pintype "passive"))
      (node (ref "R37") (pin "1") (pinfunction "1_1") (pintype "passive"))
    )
    (net (code "43") (name "39") (class "Default")
      (node (ref "JP25") (pin "19") (pinfunction "19_19") (pintype "passive"))
      (node (ref "R38") (pin "1") (pinfunction "1_1") (pintype "passive"))
    )
    (net (code "44") (name "40") (class "Default")
      (node (ref "JP25") (pin "22") (pinfunction "22_22") (pintype "passive"))
      (node (ref "R39") (pin "1") (pinfunction "1_1") (pintype "passive"))
    )
    (net (code "45") (name "41") (class "Default")
      (node (ref "JP25") (pin "21") (pinfunction "21_21") (pintype "passive"))
      (node (ref "R40") (pin "1") (pinfunction "1_1") (pintype "passive"))
    )
    (net (code "46") (name "42") (class "Default")
      (node (ref "JP25") (pin "24") (pinfunction "24_24") (pintype "passive"))
      (node (ref "R45") (pin "1") (pinfunction "1_1") (pintype "passive"))
    )
    (net (code "47") (name "43") (class "Default")
      (node (ref "JP25") (pin "23") (pinfunction "23_23") (pintype "passive"))
      (node (ref "R46") (pin "1") (pinfunction "1_1") (pintype "passive"))
    )
    (net (code "48") (name "44") (class "Default")
      (node (ref "JP25") (pin "26") (pinfunction "26_26") (pintype "passive"))
      (node (ref "R47") (pin "1") (pinfunction "1_1") (pintype "passive"))
    )
    (net (code "49") (name "45") (class "Default")
      (node (ref "JP25") (pin "25") (pinfunction "25_25") (pintype "passive"))
      (node (ref "R48") (pin "1") (pinfunction "1_1") (pintype "passive"))
    )
    (net (code "50") (name "46") (class "Default")
      (node (ref "JP25") (pin "28") (pinfunction "28_28") (pintype "passive"))
    )
    (net (code "51") (name "47") (class "Default")
      (node (ref "JP25") (pin "27") (pinfunction "27_27") (pintype "passive"))
    )
    (net (code "52") (name "48") (class "Default")
      (node (ref "JP25") (pin "30") (pinfunction "30_30") (pintype "passive"))
    )
    (net (code "53") (name "49") (class "Default")
      (node (ref "JP25") (pin "29") (pinfunction "29_29") (pintype "passive"))
    )
    (net (code "54") (name "50") (class "Default")
      (node (ref "JP25") (pin "32") (pinfunction "32_32") (pintype "passive"))
    )
    (net (code "55") (name "51") (class "Default")
      (node (ref "JP25") (pin "31") (pinfunction "31_31") (pintype "passive"))
    )
    (net (code "56") (name "52") (class "Default")
      (node (ref "JP25") (pin "34") (pinfunction "34_34") (pintype "passive"))
    )
    (net (code "57") (name "53") (class "Default")
      (node (ref "JP25") (pin "33") (pinfunction "33_33") (pintype "passive"))
    )
    (net (code "58") (name "A0") (class "Default")
      (node (ref "JP29") (pin "1") (pinfunction "1_1") (pintype "passive"))
      (node (ref "R50") (pin "1") (pinfunction "1_1") (pintype "passive"))
    )
    (net (code "59") (name "A1") (class "Default")
      (node (ref "JP29") (pin "2") (pinfunction "2_2") (pintype "passive"))
    )
    (net (code "60") (name "A2") (class "Default")
      (node (ref "JP29") (pin "3") (pinfunction "3_3") (pintype "passive"))
    )
    (net (code "61") (name "A3") (class "Default")
      (node (ref "JP29") (pin "4") (pinfunction "4_4") (pintype "passive"))
    )
    (net (code "62") (name "A4") (class "Default")
      (node (ref "JP29") (pin "5") (pinfunction "5_5") (pintype "passive"))
    )
    (net (code "63") (name "A5") (class "Default")
      (node (ref "JP29") (pin "6") (pinfunction "6_6") (pintype "passive"))
    )
    (net (code "64") (name "A6") (class "Default")
      (node (ref "JP29") (pin "7") (pinfunction "7_7") (pintype "passive"))
    )
    (net (code "65") (name "A7") (class "Default")
      (node (ref "JP29") (pin "8") (pinfunction "8_8") (pintype "passive"))
    )
    (net (code "66") (name "COM+") (class "Default")
      (node (ref "D1") (pin "A") (pinfunction "A_A") (pintype "passive"))
      (node (ref "D10") (pin "C") (pinfunction "C_C") (pintype "passive"))
      (node (ref "D11") (pin "A") (pinfunction "A_A") (pintype "passive"))
      (node (ref "D12") (pin "C") (pinfunction "C_C") (pintype "passive"))
      (node (ref "D13") (pin "A") (pinfunction "A_A") (pintype "passive"))
      (node (ref "D14") (pin "C") (pinfunction "C_C") (pintype "passive"))
      (node (ref "D15") (pin "A") (pinfunction "A_A") (pintype "passive"))
      (node (ref "D16") (pin "C") (pinfunction "C_C") (pintype "passive"))
      (node (ref "D17") (pin "A") (pinfunction "A_A") (pintype "passive"))
      (node (ref "D18") (pin "C") (pinfunction "C_C") (pintype "passive"))
      (node (ref "D19") (pin "A") (pinfunction "A_A") (pintype "passive"))
      (node (ref "D2") (pin "C") (pinfunction "C_C") (pintype "passive"))
      (node (ref "D20") (pin "C") (pinfunction "C_C") (pintype "passive"))
      (node (ref "D21") (pin "A") (pinfunction "A_A") (pintype "passive"))
      (node (ref "D22") (pin "C") (pinfunction "C_C") (pintype "passive"))
      (node (ref "D23") (pin "A") (pinfunction "A_A") (pintype "passive"))
      (node (ref "D24") (pin "C") (pinfunction "C_C") (pintype "passive"))
      (node (ref "D25") (pin "A") (pinfunction "A_A") (pintype "passive"))
      (node (ref "D26") (pin "C") (pinfunction "C_C") (pintype "passive"))
      (node (ref "D27") (pin "A") (pinfunction "A_A") (pintype "passive"))
      (node (ref "D28") (pin "C") (pinfunction "C_C") (pintype "passive"))
      (node (ref "D29") (pin "A") (pinfunction "A_A") (pintype "passive"))
      (node (ref "D3") (pin "A") (pinfunction "A_A") (pintype "passive"))
      (node (ref "D30") (pin "C") (pinfunction "C_C") (pintype "passive"))
      (node (ref "D31") (pin "A") (pinfunction "A_A") (pintype "passive"))
      (node (ref "D32") (pin "C") (pinfunction "C_C") (pintype "passive"))
      (node (ref "D33") (pin "A") (pinfunction "A_A") (pintype "passive"))
      (node (ref "D34") (pin "C") (pinfunction "C_C") (pintype "passive"))
      (node (ref "D35") (pin "A") (pinfunction "A_A") (pintype "passive"))
      (node (ref "D36") (pin "C") (pinfunction "C_C") (pintype "passive"))
      (node (ref "D37") (pin "A") (pinfunction "A_A") (pintype "passive"))
      (node (ref "D38") (pin "C") (pinfunction "C_C") (pintype "passive"))
      (node (ref "D39") (pin "A") (pinfunction "A_A") (pintype "passive"))
      (node (ref "D4") (pin "C") (pinfunction "C_C") (pintype "passive"))
      (node (ref "D40") (pin "C") (pinfunction "C_C") (pintype "passive"))
      (node (ref "D41") (pin "A") (pinfunction "A_A") (pintype "passive"))
      (node (ref "D42") (pin "C") (pinfunction "C_C") (pintype "passive"))
      (node (ref "D43") (pin "A") (pinfunction "A_A") (pintype "passive"))
      (node (ref "D44") (pin "C") (pinfunction "C_C") (pintype "passive"))
      (node (ref "D45") (pin "A") (pinfunction "A_A") (pintype "passive"))
      (node (ref "D46") (pin "C") (pinfunction "C_C") (pintype "passive"))
      (node (ref "D47") (pin "A") (pinfunction "A_A") (pintype "passive"))
      (node (ref "D48") (pin "C") (pinfunction "C_C") (pintype "passive"))
      (node (ref "D5") (pin "A") (pinfunction "A_A") (pintype "passive"))
      (node (ref "D6") (pin "C") (pinfunction "C_C") (pintype "passive"))
      (node (ref "D7") (pin "A") (pinfunction "A_A") (pintype "passive"))
      (node (ref "D8") (pin "C") (pinfunction "C_C") (pintype "passive"))
      (node (ref "D9") (pin "A") (pinfunction "A_A") (pintype "passive"))
      (node (ref "LED1") (pin "A") (pinfunction "A_A") (pintype "passive"))
      (node (ref "R1") (pin "2") (pinfunction "2_2") (pintype "passive"))
      (node (ref "R10") (pin "2") (pinfunction "2_2") (pintype "passive"))
      (node (ref "R11") (pin "2") (pinfunction "2_2") (pintype "passive"))
      (node (ref "R12") (pin "2") (pinfunction "2_2") (pintype "passive"))
      (node (ref "R17") (pin "2") (pinfunction "2_2") (pintype "passive"))
      (node (ref "R18") (pin "2") (pinfunction "2_2") (pintype "passive"))
      (node (ref "R19") (pin "2") (pinfunction "2_2") (pintype "passive"))
      (node (ref "R2") (pin "2") (pinfunction "2_2") (pintype "passive"))
      (node (ref "R20") (pin "2") (pinfunction "2_2") (pintype "passive"))
      (node (ref "R25") (pin "2") (pinfunction "2_2") (pintype "passive"))
      (node (ref "R26") (pin "2") (pinfunction "2_2") (pintype "passive"))
      (node (ref "R27") (pin "2") (pinfunction "2_2") (pintype "passive"))
      (node (ref "R28") (pin "2") (pinfunction "2_2") (pintype "passive"))
      (node (ref "R3") (pin "2") (pinfunction "2_2") (pintype "passive"))
      (node (ref "R33") (pin "2") (pinfunction "2_2") (pintype "passive"))
      (node (ref "R34") (pin "2") (pinfunction "2_2") (pintype "passive"))
      (node (ref "R35") (pin "2") (pinfunction "2_2") (pintype "passive"))
      (node (ref "R36") (pin "2") (pinfunction "2_2") (pintype "passive"))
      (node (ref "R4") (pin "2") (pinfunction "2_2") (pintype "passive"))
      (node (ref "R41") (pin "2") (pinfunction "2_2") (pintype "passive"))
      (node (ref "R42") (pin "2") (pinfunction "2_2") (pintype "passive"))
      (node (ref "R43") (pin "2") (pinfunction "2_2") (pintype "passive"))
      (node (ref "R44") (pin "2") (pinfunction "2_2") (pintype "passive"))
      (node (ref "R9") (pin "2") (pinfunction "2_2") (pintype "passive"))
      (node (ref "U7") (pin "P$7") (pinfunction "OUT+_P$7") (pintype "bidirectional"))
      (node (ref "VR25") (pin "3") (pinfunction "CW_3") (pintype "passive"))
    )
    (net (code "67") (name "COM-") (class "Default")
      (node (ref "JP1") (pin "1") (pinfunction "1_1") (pintype "passive"))
      (node (ref "JP10") (pin "1") (pinfunction "1_1") (pintype "passive"))
      (node (ref "JP11") (pin "1") (pinfunction "1_1") (pintype "passive"))
      (node (ref "JP12") (pin "1") (pinfunction "1_1") (pintype "passive"))
      (node (ref "JP13") (pin "1") (pinfunction "1_1") (pintype "passive"))
      (node (ref "JP14") (pin "1") (pinfunction "1_1") (pintype "passive"))
      (node (ref "JP15") (pin "1") (pinfunction "1_1") (pintype "passive"))
      (node (ref "JP16") (pin "1") (pinfunction "1_1") (pintype "passive"))
      (node (ref "JP17") (pin "1") (pinfunction "1_1") (pintype "passive"))
      (node (ref "JP18") (pin "1") (pinfunction "1_1") (pintype "passive"))
      (node (ref "JP19") (pin "1") (pinfunction "1_1") (pintype "passive"))
      (node (ref "JP2") (pin "1") (pinfunction "1_1") (pintype "passive"))
      (node (ref "JP20") (pin "1") (pinfunction "1_1") (pintype "passive"))
      (node (ref "JP21") (pin "1") (pinfunction "1_1") (pintype "passive"))
      (node (ref "JP22") (pin "1") (pinfunction "1_1") (pintype "passive"))
      (node (ref "JP23") (pin "1") (pinfunction "1_1") (pintype "passive"))
      (node (ref "JP24") (pin "1") (pinfunction "1_1") (pintype "passive"))
      (node (ref "JP3") (pin "1") (pinfunction "1_1") (pintype "passive"))
      (node (ref "JP4") (pin "1") (pinfunction "1_1") (pintype "passive"))
      (node (ref "JP5") (pin "1") (pinfunction "1_1") (pintype "passive"))
      (node (ref "JP6") (pin "1") (pinfunction "1_1") (pintype "passive"))
      (node (ref "JP7") (pin "1") (pinfunction "1_1") (pintype "passive"))
      (node (ref "JP8") (pin "1") (pinfunction "1_1") (pintype "passive"))
      (node (ref "JP9") (pin "1") (pinfunction "1_1") (pintype "passive"))
      (node (ref "R51") (pin "1") (pinfunction "1_1") (pintype "passive"))
      (node (ref "R57") (pin "2") (pinfunction "2_2") (pintype "passive"))
      (node (ref "U7") (pin "P$10") (pinfunction "OUT-_P$10") (pintype "bidirectional"))
    )
    (net (code "68") (name "GND") (class "Default")
      (node (ref "C1") (pin "2") (pinfunction "2_2") (pintype "passive"))
      (node (ref "C10") (pin "2") (pinfunction "2_2") (pintype "passive"))
      (node (ref "C11") (pin "2") (pinfunction "2_2") (pintype "passive"))
      (node (ref "C12") (pin "2") (pinfunction "2_2") (pintype "passive"))
      (node (ref "C13") (pin "2") (pinfunction "2_2") (pintype "passive"))
      (node (ref "C14") (pin "2") (pinfunction "2_2") (pintype "passive"))
      (node (ref "C15") (pin "2") (pinfunction "2_2") (pintype "passive"))
      (node (ref "C16") (pin "2") (pinfunction "2_2") (pintype "passive"))
      (node (ref "C17") (pin "2") (pinfunction "2_2") (pintype "passive"))
      (node (ref "C18") (pin "2") (pinfunction "2_2") (pintype "passive"))
      (node (ref "C19") (pin "2") (pinfunction "2_2") (pintype "passive"))
      (node (ref "C2") (pin "2") (pinfunction "2_2") (pintype "passive"))
      (node (ref "C20") (pin "2") (pinfunction "2_2") (pintype "passive"))
      (node (ref "C21") (pin "2") (pinfunction "2_2") (pintype "passive"))
      (node (ref "C22") (pin "2") (pinfunction "2_2") (pintype "passive"))
      (node (ref "C23") (pin "2") (pinfunction "2_2") (pintype "passive"))
      (node (ref "C24") (pin "2") (pinfunction "2_2") (pintype "passive"))
      (node (ref "C27") (pin "2") (pinfunction "2_2") (pintype "passive"))
      (node (ref "C28") (pin "-") (pinfunction "-_-") (pintype "passive"))
      (node (ref "C29") (pin "-") (pinfunction "-_-") (pintype "passive"))
      (node (ref "C3") (pin "2") (pinfunction "2_2") (pintype "passive"))
      (node (ref "C30") (pin "-") (pinfunction "-_-") (pintype "passive"))
      (node (ref "C31") (pin "2") (pinfunction "2_2") (pintype "passive"))
      (node (ref "C32") (pin "-") (pinfunction "-_-") (pintype "passive"))
      (node (ref "C33") (pin "-") (pinfunction "-_-") (pintype "passive"))
      (node (ref "C4") (pin "2") (pinfunction "2_2") (pintype "passive"))
      (node (ref "C5") (pin "2") (pinfunction "2_2") (pintype "passive"))
      (node (ref "C6") (pin "2") (pinfunction "2_2") (pintype "passive"))
      (node (ref "C7") (pin "2") (pinfunction "2_2") (pintype "passive"))
      (node (ref "C8") (pin "2") (pinfunction "2_2") (pintype "passive"))
      (node (ref "C9") (pin "2") (pinfunction "2_2") (pintype "passive"))
      (node (ref "J1") (pin "1") (pinfunction "1_1") (pintype "passive"))
      (node (ref "JP25") (pin "35") (pinfunction "35_35") (pintype "passive"))
      (node (ref "JP25") (pin "36") (pinfunction "36_36") (pintype "passive"))
      (node (ref "JP26") (pin "7") (pinfunction "7_7") (pintype "passive"))
      (node (ref "JP33") (pin "1") (pinfunction "1_1") (pintype "passive"))
      (node (ref "JP33") (pin "2") (pinfunction "2_2") (pintype "passive"))
      (node (ref "JP33") (pin "3") (pinfunction "3_3") (pintype "passive"))
      (node (ref "JP33") (pin "4") (pinfunction "4_4") (pintype "passive"))
      (node (ref "JP33") (pin "5") (pinfunction "5_5") (pintype "passive"))
      (node (ref "JP33") (pin "6") (pinfunction "6_6") (pintype "passive"))
      (node (ref "JP33") (pin "7") (pinfunction "7_7") (pintype "passive"))
      (node (ref "JP33") (pin "8") (pinfunction "8_8") (pintype "passive"))
      (node (ref "JP34") (pin "3") (pinfunction "3_3") (pintype "passive"))
      (node (ref "JP34") (pin "4") (pinfunction "4_4") (pintype "passive"))
      (node (ref "R49") (pin "1") (pinfunction "1_1") (pintype "passive"))
      (node (ref "R54") (pin "1") (pinfunction "1_1") (pintype "passive"))
      (node (ref "R55") (pin "1") (pinfunction "1_1") (pintype "passive"))
      (node (ref "U1") (pin "12") (pinfunction "GND_12") (pintype "power_in"))
      (node (ref "U2") (pin "12") (pinfunction "GND_12") (pintype "power_in"))
      (node (ref "U3") (pin "12") (pinfunction "GND_12") (pintype "power_in"))
      (node (ref "U4") (pin "12") (pinfunction "GND_12") (pintype "power_in"))
      (node (ref "U5") (pin "12") (pinfunction "GND_12") (pintype "power_in"))
      (node (ref "U6") (pin "12") (pinfunction "GND_12") (pintype "power_in"))
      (node (ref "U7") (pin "P$13") (pinfunction "GND1_P$13") (pintype "bidirectional"))
      (node (ref "U7") (pin "P$16") (pinfunction "MODE2_P$16") (pintype "bidirectional"))
      (node (ref "U7") (pin "P$17") (pinfunction "EPAD_P$17") (pintype "bidirectional"))
      (node (ref "U7") (pin "P$4") (pinfunction "GND_P$4") (pintype "bidirectional"))
      (node (ref "VR1") (pin "3") (pinfunction "CW_3") (pintype "passive"))
      (node (ref "VR10") (pin "3") (pinfunction "CW_3") (pintype "passive"))
      (node (ref "VR11") (pin "3") (pinfunction "CW_3") (pintype "passive"))
      (node (ref "VR12") (pin "3") (pinfunction "CW_3") (pintype "passive"))
      (node (ref "VR13") (pin "3") (pinfunction "CW_3") (pintype "passive"))
      (node (ref "VR14") (pin "3") (pinfunction "CW_3") (pintype "passive"))
      (node (ref "VR15") (pin "3") (pinfunction "CW_3") (pintype "passive"))
      (node (ref "VR16") (pin "3") (pinfunction "CW_3") (pintype "passive"))
      (node (ref "VR17") (pin "3") (pinfunction "CW_3") (pintype "passive"))
      (node (ref "VR18") (pin "3") (pinfunction "CW_3") (pintype "passive"))
      (node (ref "VR19") (pin "3") (pinfunction "CW_3") (pintype "passive"))
      (node (ref "VR2") (pin "3") (pinfunction "CW_3") (pintype "passive"))
      (node (ref "VR20") (pin "3") (pinfunction "CW_3") (pintype "passive"))
      (node (ref "VR21") (pin "3") (pinfunction "CW_3") (pintype "passive"))
      (node (ref "VR22") (pin "3") (pinfunction "CW_3") (pintype "passive"))
      (node (ref "VR23") (pin "3") (pinfunction "CW_3") (pintype "passive"))
      (node (ref "VR24") (pin "3") (pinfunction "CW_3") (pintype "passive"))
      (node (ref "VR3") (pin "3") (pinfunction "CW_3") (pintype "passive"))
      (node (ref "VR4") (pin "3") (pinfunction "CW_3") (pintype "passive"))
      (node (ref "VR5") (pin "3") (pinfunction "CW_3") (pintype "passive"))
      (node (ref "VR6") (pin "3") (pinfunction "CW_3") (pintype "passive"))
      (node (ref "VR7") (pin "3") (pinfunction "CW_3") (pintype "passive"))
      (node (ref "VR8") (pin "3") (pinfunction "CW_3") (pintype "passive"))
      (node (ref "VR9") (pin "3") (pinfunction "CW_3") (pintype "passive"))
    )
    (net (code "69") (name "Net-(JP30-Pad1)") (class "Default")
      (node (ref "JP30") (pin "1") (pinfunction "1_1") (pintype "passive"))
      (node (ref "JP31") (pin "1") (pinfunction "1_1") (pintype "passive"))
    )
    (net (code "70") (name "Net-(JP30-Pad2)") (class "Default")
      (node (ref "JP30") (pin "2") (pinfunction "2_2") (pintype "passive"))
      (node (ref "JP31") (pin "2") (pinfunction "2_2") (pintype "passive"))
    )
    (net (code "71") (name "Net-(JP30-Pad3)") (class "Default")
      (node (ref "JP30") (pin "3") (pinfunction "3_3") (pintype "passive"))
      (node (ref "JP31") (pin "3") (pinfunction "3_3") (pintype "passive"))
    )
    (net (code "72") (name "Net-(JP30-Pad4)") (class "Default")
      (node (ref "JP30") (pin "4") (pinfunction "4_4") (pintype "passive"))
      (node (ref "JP31") (pin "4") (pinfunction "4_4") (pintype "passive"))
    )
    (net (code "73") (name "Net-(JP30-Pad5)") (class "Default")
      (node (ref "JP30") (pin "5") (pinfunction "5_5") (pintype "passive"))
      (node (ref "JP31") (pin "5") (pinfunction "5_5") (pintype "passive"))
    )
    (net (code "74") (name "Net-(JP30-Pad6)") (class "Default")
      (node (ref "JP30") (pin "6") (pinfunction "6_6") (pintype "passive"))
      (node (ref "JP31") (pin "6") (pinfunction "6_6") (pintype "passive"))
    )
    (net (code "75") (name "Net-(JP30-Pad7)") (class "Default")
      (node (ref "JP30") (pin "7") (pinfunction "7_7") (pintype "passive"))
      (node (ref "JP31") (pin "7") (pinfunction "7_7") (pintype "passive"))
    )
    (net (code "76") (name "Net-(JP30-Pad8)") (class "Default")
      (node (ref "JP30") (pin "8") (pinfunction "8_8") (pintype "passive"))
      (node (ref "JP31") (pin "8") (pinfunction "8_8") (pintype "passive"))
    )
    (net (code "77") (name "Net-(LED1-PadC)") (class "Default")
      (node (ref "LED1") (pin "C") (pinfunction "C_C") (pintype "passive"))
      (node (ref "R51") (pin "2") (pinfunction "2_2") (pintype "passive"))
    )
    (net (code "78") (name "Net-(LED2-PadC)") (class "Default")
      (node (ref "LED2") (pin "C") (pinfunction "C_C") (pintype "passive"))
      (node (ref "R52") (pin "2") (pinfunction "2_2") (pintype "passive"))
    )
    (net (code "79") (name "Net-(LED3-PadC)") (class "Default")
      (node (ref "LED3") (pin "C") (pinfunction "C_C") (pintype "passive"))
      (node (ref "R53") (pin "2") (pinfunction "2_2") (pintype "passive"))
    )
    (net (code "80") (name "Net-(LED4-PadC)") (class "Default")
      (node (ref "LED4") (pin "C") (pinfunction "C_C") (pintype "passive"))
      (node (ref "R54") (pin "2") (pinfunction "2_2") (pintype "passive"))
    )
    (net (code "81") (name "Net-(LED5-PadC)") (class "Default")
      (node (ref "LED5") (pin "C") (pinfunction "C_C") (pintype "passive"))
      (node (ref "R55") (pin "2") (pinfunction "2_2") (pintype "passive"))
    )
    (net (code "82") (name "Net-(U1A-+IN)") (class "Default")
      (node (ref "U1") (pin "7") (pinfunction "+IN_7") (pintype "input"))
      (node (ref "VR2") (pin "2") (pinfunction "WIPER_2") (pintype "passive"))
    )
    (net (code "83") (name "Net-(U1A-OUT)") (class "Default")
      (node (ref "C2") (pin "1") (pinfunction "1_1") (pintype "passive"))
      (node (ref "R6") (pin "2") (pinfunction "2_2") (pintype "passive"))
      (node (ref "U1") (pin "1") (pinfunction "OUT_1") (pintype "output"))
    )
    (net (code "84") (name "Net-(U1B-+IN)") (class "Default")
      (node (ref "U1") (pin "5") (pinfunction "+IN_5") (pintype "input"))
      (node (ref "VR1") (pin "2") (pinfunction "WIPER_2") (pintype "passive"))
    )
    (net (code "85") (name "Net-(U1B-OUT)") (class "Default")
      (node (ref "C1") (pin "1") (pinfunction "1_1") (pintype "passive"))
      (node (ref "R5") (pin "2") (pinfunction "2_2") (pintype "passive"))
      (node (ref "U1") (pin "2") (pinfunction "OUT_2") (pintype "output"))
    )
    (net (code "86") (name "Net-(U1C-+IN)") (class "Default")
      (node (ref "U1") (pin "9") (pinfunction "+IN_9") (pintype "input"))
      (node (ref "VR3") (pin "2") (pinfunction "WIPER_2") (pintype "passive"))
    )
    (net (code "87") (name "Net-(U1C-OUT)") (class "Default")
      (node (ref "C3") (pin "1") (pinfunction "1_1") (pintype "passive"))
      (node (ref "R7") (pin "2") (pinfunction "2_2") (pintype "passive"))
      (node (ref "U1") (pin "14") (pinfunction "OUT_14") (pintype "output"))
    )
    (net (code "88") (name "Net-(U1D-+IN)") (class "Default")
      (node (ref "U1") (pin "11") (pinfunction "+IN_11") (pintype "input"))
      (node (ref "VR4") (pin "2") (pinfunction "WIPER_2") (pintype "passive"))
    )
    (net (code "89") (name "Net-(U1D-OUT)") (class "Default")
      (node (ref "C4") (pin "1") (pinfunction "1_1") (pintype "passive"))
      (node (ref "R8") (pin "2") (pinfunction "2_2") (pintype "passive"))
      (node (ref "U1") (pin "13") (pinfunction "OUT_13") (pintype "output"))
    )
    (net (code "90") (name "Net-(U2A-+IN)") (class "Default")
      (node (ref "U2") (pin "7") (pinfunction "+IN_7") (pintype "input"))
      (node (ref "VR6") (pin "2") (pinfunction "WIPER_2") (pintype "passive"))
    )
    (net (code "91") (name "Net-(U2A-OUT)") (class "Default")
      (node (ref "C6") (pin "1") (pinfunction "1_1") (pintype "passive"))
      (node (ref "R14") (pin "2") (pinfunction "2_2") (pintype "passive"))
      (node (ref "U2") (pin "1") (pinfunction "OUT_1") (pintype "output"))
    )
    (net (code "92") (name "Net-(U2B-+IN)") (class "Default")
      (node (ref "U2") (pin "5") (pinfunction "+IN_5") (pintype "input"))
      (node (ref "VR5") (pin "2") (pinfunction "WIPER_2") (pintype "passive"))
    )
    (net (code "93") (name "Net-(U2B-OUT)") (class "Default")
      (node (ref "C5") (pin "1") (pinfunction "1_1") (pintype "passive"))
      (node (ref "R13") (pin "2") (pinfunction "2_2") (pintype "passive"))
      (node (ref "U2") (pin "2") (pinfunction "OUT_2") (pintype "output"))
    )
    (net (code "94") (name "Net-(U2C-+IN)") (class "Default")
      (node (ref "U2") (pin "9") (pinfunction "+IN_9") (pintype "input"))
      (node (ref "VR7") (pin "2") (pinfunction "WIPER_2") (pintype "passive"))
    )
    (net (code "95") (name "Net-(U2C-OUT)") (class "Default")
      (node (ref "C7") (pin "1") (pinfunction "1_1") (pintype "passive"))
      (node (ref "R15") (pin "2") (pinfunction "2_2") (pintype "passive"))
      (node (ref "U2") (pin "14") (pinfunction "OUT_14") (pintype "output"))
    )
    (net (code "96") (name "Net-(U2D-+IN)") (class "Default")
      (node (ref "U2") (pin "11") (pinfunction "+IN_11") (pintype "input"))
      (node (ref "VR8") (pin "2") (pinfunction "WIPER_2") (pintype "passive"))
    )
    (net (code "97") (name "Net-(U2D-OUT)") (class "Default")
      (node (ref "C8") (pin "1") (pinfunction "1_1") (pintype "passive"))
      (node (ref "R16") (pin "2") (pinfunction "2_2") (pintype "passive"))
      (node (ref "U2") (pin "13") (pinfunction "OUT_13") (pintype "output"))
    )
    (net (code "98") (name "Net-(U3A-+IN)") (class "Default")
      (node (ref "U3") (pin "7") (pinfunction "+IN_7") (pintype "input"))
      (node (ref "VR10") (pin "2") (pinfunction "WIPER_2") (pintype "passive"))
    )
    (net (code "99") (name "Net-(U3A-OUT)") (class "Default")
      (node (ref "C10") (pin "1") (pinfunction "1_1") (pintype "passive"))
      (node (ref "R22") (pin "2") (pinfunction "2_2") (pintype "passive"))
      (node (ref "U3") (pin "1") (pinfunction "OUT_1") (pintype "output"))
    )
    (net (code "100") (name "Net-(U3B-+IN)") (class "Default")
      (node (ref "U3") (pin "5") (pinfunction "+IN_5") (pintype "input"))
      (node (ref "VR9") (pin "2") (pinfunction "WIPER_2") (pintype "passive"))
    )
    (net (code "101") (name "Net-(U3B-OUT)") (class "Default")
      (node (ref "C9") (pin "1") (pinfunction "1_1") (pintype "passive"))
      (node (ref "R21") (pin "2") (pinfunction "2_2") (pintype "passive"))
      (node (ref "U3") (pin "2") (pinfunction "OUT_2") (pintype "output"))
    )
    (net (code "102") (name "Net-(U3C-+IN)") (class "Default")
      (node (ref "U3") (pin "9") (pinfunction "+IN_9") (pintype "input"))
      (node (ref "VR11") (pin "2") (pinfunction "WIPER_2") (pintype "passive"))
    )
    (net (code "103") (name "Net-(U3C-OUT)") (class "Default")
      (node (ref "C11") (pin "1") (pinfunction "1_1") (pintype "passive"))
      (node (ref "R23") (pin "2") (pinfunction "2_2") (pintype "passive"))
      (node (ref "U3") (pin "14") (pinfunction "OUT_14") (pintype "output"))
    )
    (net (code "104") (name "Net-(U3D-+IN)") (class "Default")
      (node (ref "U3") (pin "11") (pinfunction "+IN_11") (pintype "input"))
      (node (ref "VR12") (pin "2") (pinfunction "WIPER_2") (pintype "passive"))
    )
    (net (code "105") (name "Net-(U3D-OUT)") (class "Default")
      (node (ref "C12") (pin "1") (pinfunction "1_1") (pintype "passive"))
      (node (ref "R24") (pin "2") (pinfunction "2_2") (pintype "passive"))
      (node (ref "U3") (pin "13") (pinfunction "OUT_13") (pintype "output"))
    )
    (net (code "106") (name "Net-(U4A-+IN)") (class "Default")
      (node (ref "U4") (pin "7") (pinfunction "+IN_7") (pintype "input"))
      (node (ref "VR14") (pin "2") (pinfunction "WIPER_2") (pintype "passive"))
    )
    (net (code "107") (name "Net-(U4A-OUT)") (class "Default")
      (node (ref "C14") (pin "1") (pinfunction "1_1") (pintype "passive"))
      (node (ref "R30") (pin "2") (pinfunction "2_2") (pintype "passive"))
      (node (ref "U4") (pin "1") (pinfunction "OUT_1") (pintype "output"))
    )
    (net (code "108") (name "Net-(U4B-+IN)") (class "Default")
      (node (ref "U4") (pin "5") (pinfunction "+IN_5") (pintype "input"))
      (node (ref "VR13") (pin "2") (pinfunction "WIPER_2") (pintype "passive"))
    )
    (net (code "109") (name "Net-(U4B-OUT)") (class "Default")
      (node (ref "C13") (pin "1") (pinfunction "1_1") (pintype "passive"))
      (node (ref "R29") (pin "2") (pinfunction "2_2") (pintype "passive"))
      (node (ref "U4") (pin "2") (pinfunction "OUT_2") (pintype "output"))
    )
    (net (code "110") (name "Net-(U4C-+IN)") (class "Default")
      (node (ref "U4") (pin "9") (pinfunction "+IN_9") (pintype "input"))
      (node (ref "VR15") (pin "2") (pinfunction "WIPER_2") (pintype "passive"))
    )
    (net (code "111") (name "Net-(U4C-OUT)") (class "Default")
      (node (ref "C15") (pin "1") (pinfunction "1_1") (pintype "passive"))
      (node (ref "R31") (pin "2") (pinfunction "2_2") (pintype "passive"))
      (node (ref "U4") (pin "14") (pinfunction "OUT_14") (pintype "output"))
    )
    (net (code "112") (name "Net-(U4D-+IN)") (class "Default")
      (node (ref "U4") (pin "11") (pinfunction "+IN_11") (pintype "input"))
      (node (ref "VR16") (pin "2") (pinfunction "WIPER_2") (pintype "passive"))
    )
    (net (code "113") (name "Net-(U4D-OUT)") (class "Default")
      (node (ref "C16") (pin "1") (pinfunction "1_1") (pintype "passive"))
      (node (ref "R32") (pin "2") (pinfunction "2_2") (pintype "passive"))
      (node (ref "U4") (pin "13") (pinfunction "OUT_13") (pintype "output"))
    )
    (net (code "114") (name "Net-(U5A-+IN)") (class "Default")
      (node (ref "U5") (pin "7") (pinfunction "+IN_7") (pintype "input"))
      (node (ref "VR18") (pin "2") (pinfunction "WIPER_2") (pintype "passive"))
    )
    (net (code "115") (name "Net-(U5A-OUT)") (class "Default")
      (node (ref "C18") (pin "1") (pinfunction "1_1") (pintype "passive"))
      (node (ref "R38") (pin "2") (pinfunction "2_2") (pintype "passive"))
      (node (ref "U5") (pin "1") (pinfunction "OUT_1") (pintype "output"))
    )
    (net (code "116") (name "Net-(U5B-+IN)") (class "Default")
      (node (ref "U5") (pin "5") (pinfunction "+IN_5") (pintype "input"))
      (node (ref "VR17") (pin "2") (pinfunction "WIPER_2") (pintype "passive"))
    )
    (net (code "117") (name "Net-(U5B-OUT)") (class "Default")
      (node (ref "C17") (pin "1") (pinfunction "1_1") (pintype "passive"))
      (node (ref "R37") (pin "2") (pinfunction "2_2") (pintype "passive"))
      (node (ref "U5") (pin "2") (pinfunction "OUT_2") (pintype "output"))
    )
    (net (code "118") (name "Net-(U5C-+IN)") (class "Default")
      (node (ref "U5") (pin "9") (pinfunction "+IN_9") (pintype "input"))
      (node (ref "VR19") (pin "2") (pinfunction "WIPER_2") (pintype "passive"))
    )
    (net (code "119") (name "Net-(U5C-OUT)") (class "Default")
      (node (ref "C19") (pin "1") (pinfunction "1_1") (pintype "passive"))
      (node (ref "R39") (pin "2") (pinfunction "2_2") (pintype "passive"))
      (node (ref "U5") (pin "14") (pinfunction "OUT_14") (pintype "output"))
    )
    (net (code "120") (name "Net-(U5D-+IN)") (class "Default")
      (node (ref "U5") (pin "11") (pinfunction "+IN_11") (pintype "input"))
      (node (ref "VR20") (pin "2") (pinfunction "WIPER_2") (pintype "passive"))
    )
    (net (code "121") (name "Net-(U5D-OUT)") (class "Default")
      (node (ref "C20") (pin "1") (pinfunction "1_1") (pintype "passive"))
      (node (ref "R40") (pin "2") (pinfunction "2_2") (pintype "passive"))
      (node (ref "U5") (pin "13") (pinfunction "OUT_13") (pintype "output"))
    )
    (net (code "122") (name "Net-(U6A-+IN)") (class "Default")
      (node (ref "U6") (pin "7") (pinfunction "+IN_7") (pintype "input"))
      (node (ref "VR22") (pin "2") (pinfunction "WIPER_2") (pintype "passive"))
    )
    (net (code "123") (name "Net-(U6A-OUT)") (class "Default")
      (node (ref "C22") (pin "1") (pinfunction "1_1") (pintype "passive"))
      (node (ref "R46") (pin "2") (pinfunction "2_2") (pintype "passive"))
      (node (ref "U6") (pin "1") (pinfunction "OUT_1") (pintype "output"))
    )
    (net (code "124") (name "Net-(U6B-+IN)") (class "Default")
      (node (ref "U6") (pin "5") (pinfunction "+IN_5") (pintype "input"))
      (node (ref "VR21") (pin "2") (pinfunction "WIPER_2") (pintype "passive"))
    )
    (net (code "125") (name "Net-(U6B-OUT)") (class "Default")
      (node (ref "C21") (pin "1") (pinfunction "1_1") (pintype "passive"))
      (node (ref "R45") (pin "2") (pinfunction "2_2") (pintype "passive"))
      (node (ref "U6") (pin "2") (pinfunction "OUT_2") (pintype "output"))
    )
    (net (code "126") (name "Net-(U6C-+IN)") (class "Default")
      (node (ref "U6") (pin "9") (pinfunction "+IN_9") (pintype "input"))
      (node (ref "VR23") (pin "2") (pinfunction "WIPER_2") (pintype "passive"))
    )
    (net (code "127") (name "Net-(U6C-OUT)") (class "Default")
      (node (ref "C23") (pin "1") (pinfunction "1_1") (pintype "passive"))
      (node (ref "R47") (pin "2") (pinfunction "2_2") (pintype "passive"))
      (node (ref "U6") (pin "14") (pinfunction "OUT_14") (pintype "output"))
    )
    (net (code "128") (name "Net-(U6D-+IN)") (class "Default")
      (node (ref "U6") (pin "11") (pinfunction "+IN_11") (pintype "input"))
      (node (ref "VR24") (pin "2") (pinfunction "WIPER_2") (pintype "passive"))
    )
    (net (code "129") (name "Net-(U6D-OUT)") (class "Default")
      (node (ref "C24") (pin "1") (pinfunction "1_1") (pintype "passive"))
      (node (ref "R48") (pin "2") (pinfunction "2_2") (pintype "passive"))
      (node (ref "U6") (pin "13") (pinfunction "OUT_13") (pintype "output"))
    )
    (net (code "130") (name "Net-(U7-CP1)") (class "Default")
      (node (ref "C25") (pin "2") (pinfunction "2_2") (pintype "passive"))
      (node (ref "U7") (pin "P$11") (pinfunction "CP1_P$11") (pintype "bidirectional"))
    )
    (net (code "131") (name "Net-(U7-CP2)") (class "Default")
      (node (ref "C25") (pin "1") (pinfunction "1_1") (pintype "passive"))
      (node (ref "U7") (pin "P$12") (pinfunction "CP2_P$12") (pintype "bidirectional"))
    )
    (net (code "132") (name "Net-(U7-SENSE)") (class "Default")
      (node (ref "R49") (pin "2") (pinfunction "2_2") (pintype "passive"))
      (node (ref "U7") (pin "P$8") (pinfunction "SENSE_P$8") (pintype "bidirectional"))
    )
    (net (code "133") (name "Net-(U7-VCP)") (class "Default")
      (node (ref "C26") (pin "1") (pinfunction "1_1") (pintype "passive"))
      (node (ref "U7") (pin "P$14") (pinfunction "VCP_P$14") (pintype "bidirectional"))
    )
    (net (code "134") (name "Net-(U7-VPROPI)") (class "Default")
      (node (ref "R50") (pin "2") (pinfunction "2_2") (pintype "passive"))
      (node (ref "U7") (pin "P$15") (pinfunction "VPROPI_P$15") (pintype "bidirectional"))
    )
    (net (code "135") (name "Net-(VR1-CCW)") (class "Default")
      (node (ref "D1") (pin "C") (pinfunction "C_C") (pintype "passive"))
      (node (ref "D2") (pin "A") (pinfunction "A_A") (pintype "passive"))
      (node (ref "JP1") (pin "2") (pinfunction "2_2") (pintype "passive"))
      (node (ref "R1") (pin "1") (pinfunction "1_1") (pintype "passive"))
      (node (ref "VR1") (pin "1") (pinfunction "CCW_1") (pintype "passive"))
    )
    (net (code "136") (name "Net-(VR2-CCW)") (class "Default")
      (node (ref "D3") (pin "C") (pinfunction "C_C") (pintype "passive"))
      (node (ref "D4") (pin "A") (pinfunction "A_A") (pintype "passive"))
      (node (ref "JP2") (pin "2") (pinfunction "2_2") (pintype "passive"))
      (node (ref "R2") (pin "1") (pinfunction "1_1") (pintype "passive"))
      (node (ref "VR2") (pin "1") (pinfunction "CCW_1") (pintype "passive"))
    )
    (net (code "137") (name "Net-(VR3-CCW)") (class "Default")
      (node (ref "D5") (pin "C") (pinfunction "C_C") (pintype "passive"))
      (node (ref "D6") (pin "A") (pinfunction "A_A") (pintype "passive"))
      (node (ref "JP3") (pin "2") (pinfunction "2_2") (pintype "passive"))
      (node (ref "R3") (pin "1") (pinfunction "1_1") (pintype "passive"))
      (node (ref "VR3") (pin "1") (pinfunction "CCW_1") (pintype "passive"))
    )
    (net (code "138") (name "Net-(VR4-CCW)") (class "Default")
      (node (ref "D7") (pin "C") (pinfunction "C_C") (pintype "passive"))
      (node (ref "D8") (pin "A") (pinfunction "A_A") (pintype "passive"))
      (node (ref "JP4") (pin "2") (pinfunction "2_2") (pintype "passive"))
      (node (ref "R4") (pin "1") (pinfunction "1_1") (pintype "passive"))
      (node (ref "VR4") (pin "1") (pinfunction "CCW_1") (pintype "passive"))
    )
    (net (code "139") (name "Net-(VR5-CCW)") (class "Default")
      (node (ref "D10") (pin "A") (pinfunction "A_A") (pintype "passive"))
      (node (ref "D9") (pin "C") (pinfunction "C_C") (pintype "passive"))
      (node (ref "JP5") (pin "2") (pinfunction "2_2") (pintype "passive"))
      (node (ref "R9") (pin "1") (pinfunction "1_1") (pintype "passive"))
      (node (ref "VR5") (pin "1") (pinfunction "CCW_1") (pintype "passive"))
    )
    (net (code "140") (name "Net-(VR6-CCW)") (class "Default")
      (node (ref "D11") (pin "C") (pinfunction "C_C") (pintype "passive"))
      (node (ref "D12") (pin "A") (pinfunction "A_A") (pintype "passive"))
      (node (ref "JP6") (pin "2") (pinfunction "2_2") (pintype "passive"))
      (node (ref "R10") (pin "1") (pinfunction "1_1") (pintype "passive"))
      (node (ref "VR6") (pin "1") (pinfunction "CCW_1") (pintype "passive"))
    )
    (net (code "141") (name "Net-(VR7-CCW)") (class "Default")
      (node (ref "D13") (pin "C") (pinfunction "C_C") (pintype "passive"))
      (node (ref "D14") (pin "A") (pinfunction "A_A") (pintype "passive"))
      (node (ref "JP7") (pin "2") (pinfunction "2_2") (pintype "passive"))
      (node (ref "R11") (pin "1") (pinfunction "1_1") (pintype "passive"))
      (node (ref "VR7") (pin "1") (pinfunction "CCW_1") (pintype "passive"))
    )
    (net (code "142") (name "Net-(VR8-CCW)") (class "Default")
      (node (ref "D15") (pin "C") (pinfunction "C_C") (pintype "passive"))
      (node (ref "D16") (pin "A") (pinfunction "A_A") (pintype "passive"))
      (node (ref "JP8") (pin "2") (pinfunction "2_2") (pintype "passive"))
      (node (ref "R12") (pin "1") (pinfunction "1_1") (pintype "passive"))
      (node (ref "VR8") (pin "1") (pinfunction "CCW_1") (pintype "passive"))
    )
    (net (code "143") (name "Net-(VR9-CCW)") (class "Default")
      (node (ref "D17") (pin "C") (pinfunction "C_C") (pintype "passive"))
      (node (ref "D18") (pin "A") (pinfunction "A_A") (pintype "passive"))
      (node (ref "JP9") (pin "2") (pinfunction "2_2") (pintype "passive"))
      (node (ref "R17") (pin "1") (pinfunction "1_1") (pintype "passive"))
      (node (ref "VR9") (pin "1") (pinfunction "CCW_1") (pintype "passive"))
    )
    (net (code "144") (name "Net-(VR10-CCW)") (class "Default")
      (node (ref "D19") (pin "C") (pinfunction "C_C") (pintype "passive"))
      (node (ref "D20") (pin "A") (pinfunction "A_A") (pintype "passive"))
      (node (ref "JP10") (pin "2") (pinfunction "2_2") (pintype "passive"))
      (node (ref "R18") (pin "1") (pinfunction "1_1") (pintype "passive"))
      (node (ref "VR10") (pin "1") (pinfunction "CCW_1") (pintype "passive"))
    )
    (net (code "145") (name "Net-(VR11-CCW)") (class "Default")
      (node (ref "D21") (pin "C") (pinfunction "C_C") (pintype "passive"))
      (node (ref "D22") (pin "A") (pinfunction "A_A") (pintype "passive"))
      (node (ref "JP11") (pin "2") (pinfunction "2_2") (pintype "passive"))
      (node (ref "R19") (pin "1") (pinfunction "1_1") (pintype "passive"))
      (node (ref "VR11") (pin "1") (pinfunction "CCW_1") (pintype "passive"))
    )
    (net (code "146") (name "Net-(VR12-CCW)") (class "Default")
      (node (ref "D23") (pin "C") (pinfunction "C_C") (pintype "passive"))
      (node (ref "D24") (pin "A") (pinfunction "A_A") (pintype "passive"))
      (node (ref "JP12") (pin "2") (pinfunction "2_2") (pintype "passive"))
      (node (ref "R20") (pin "1") (pinfunction "1_1") (pintype "passive"))
      (node (ref "VR12") (pin "1") (pinfunction "CCW_1") (pintype "passive"))
    )
    (net (code "147") (name "Net-(VR13-CCW)") (class "Default")
      (node (ref "D25") (pin "C") (pinfunction "C_C") (pintype "passive"))
      (node (ref "D26") (pin "A") (pinfunction "A_A") (pintype "passive"))
      (node (ref "JP13") (pin "2") (pinfunction "2_2") (pintype "passive"))
      (node (ref "R25") (pin "1") (pinfunction "1_1") (pintype "passive"))
      (node (ref "VR13") (pin "1") (pinfunction "CCW_1") (pintype "passive"))
    )
    (net (code "148") (name "Net-(VR14-CCW)") (class "Default")
      (node (ref "D27") (pin "C") (pinfunction "C_C") (pintype "passive"))
      (node (ref "D28") (pin "A") (pinfunction "A_A") (pintype "passive"))
      (node (ref "JP14") (pin "2") (pinfunction "2_2") (pintype "passive"))
      (node (ref "R26") (pin "1") (pinfunction "1_1") (pintype "passive"))
      (node (ref "VR14") (pin "1") (pinfunction "CCW_1") (pintype "passive"))
    )
    (net (code "149") (name "Net-(VR15-CCW)") (class "Default")
      (node (ref "D29") (pin "C") (pinfunction "C_C") (pintype "passive"))
      (node (ref "D30") (pin "A") (pinfunction "A_A") (pintype "passive"))
      (node (ref "JP15") (pin "2") (pinfunction "2_2") (pintype "passive"))
      (node (ref "R27") (pin "1") (pinfunction "1_1") (pintype "passive"))
      (node (ref "VR15") (pin "1") (pinfunction "CCW_1") (pintype "passive"))
    )
    (net (code "150") (name "Net-(VR16-CCW)") (class "Default")
      (node (ref "D31") (pin "C") (pinfunction "C_C") (pintype "passive"))
      (node (ref "D32") (pin "A") (pinfunction "A_A") (pintype "passive"))
      (node (ref "JP16") (pin "2") (pinfunction "2_2") (pintype "passive"))
      (node (ref "R28") (pin "1") (pinfunction "1_1") (pintype "passive"))
      (node (ref "VR16") (pin "1") (pinfunction "CCW_1") (pintype "passive"))
    )
    (net (code "151") (name "Net-(VR17-CCW)") (class "Default")
      (node (ref "D33") (pin "C") (pinfunction "C_C") (pintype "passive"))
      (node (ref "D34") (pin "A") (pinfunction "A_A") (pintype "passive"))
      (node (ref "JP17") (pin "2") (pinfunction "2_2") (pintype "passive"))
      (node (ref "R33") (pin "1") (pinfunction "1_1") (pintype "passive"))
      (node (ref "VR17") (pin "1") (pinfunction "CCW_1") (pintype "passive"))
    )
    (net (code "152") (name "Net-(VR18-CCW)") (class "Default")
      (node (ref "D35") (pin "C") (pinfunction "C_C") (pintype "passive"))
      (node (ref "D36") (pin "A") (pinfunction "A_A") (pintype "passive"))
      (node (ref "JP18") (pin "2") (pinfunction "2_2") (pintype "passive"))
      (node (ref "R34") (pin "1") (pinfunction "1_1") (pintype "passive"))
      (node (ref "VR18") (pin "1") (pinfunction "CCW_1") (pintype "passive"))
    )
    (net (code "153") (name "Net-(VR19-CCW)") (class "Default")
      (node (ref "D37") (pin "C") (pinfunction "C_C") (pintype "passive"))
      (node (ref "D38") (pin "A") (pinfunction "A_A") (pintype "passive"))
      (node (ref "JP19") (pin "2") (pinfunction "2_2") (pintype "passive"))
      (node (ref "R35") (pin "1") (pinfunction "1_1") (pintype "passive"))
      (node (ref "VR19") (pin "1") (pinfunction "CCW_1") (pintype "passive"))
    )
    (net (code "154") (name "Net-(VR20-CCW)") (class "Default")
      (node (ref "D39") (pin "C") (pinfunction "C_C") (pintype "passive"))
      (node (ref "D40") (pin "A") (pinfunction "A_A") (pintype "passive"))
      (node (ref "JP20") (pin "2") (pinfunction "2_2") (pintype "passive"))
      (node (ref "R36") (pin "1") (pinfunction "1_1") (pintype "passive"))
      (node (ref "VR20") (pin "1") (pinfunction "CCW_1") (pintype "passive"))
    )
    (net (code "155") (name "Net-(VR21-CCW)") (class "Default")
      (node (ref "D41") (pin "C") (pinfunction "C_C") (pintype "passive"))
      (node (ref "D42") (pin "A") (pinfunction "A_A") (pintype "passive"))
      (node (ref "JP21") (pin "2") (pinfunction "2_2") (pintype "passive"))
      (node (ref "R41") (pin "1") (pinfunction "1_1") (pintype "passive"))
      (node (ref "VR21") (pin "1") (pinfunction "CCW_1") (pintype "passive"))
    )
    (net (code "156") (name "Net-(VR22-CCW)") (class "Default")
      (node (ref "D43") (pin "C") (pinfunction "C_C") (pintype "passive"))
      (node (ref "D44") (pin "A") (pinfunction "A_A") (pintype "passive"))
      (node (ref "JP22") (pin "2") (pinfunction "2_2") (pintype "passive"))
      (node (ref "R42") (pin "1") (pinfunction "1_1") (pintype "passive"))
      (node (ref "VR22") (pin "1") (pinfunction "CCW_1") (pintype "passive"))
    )
    (net (code "157") (name "Net-(VR23-CCW)") (class "Default")
      (node (ref "D45") (pin "C") (pinfunction "C_C") (pintype "passive"))
      (node (ref "D46") (pin "A") (pinfunction "A_A") (pintype "passive"))
      (node (ref "JP23") (pin "2") (pinfunction "2_2") (pintype "passive"))
      (node (ref "R43") (pin "1") (pinfunction "1_1") (pintype "passive"))
      (node (ref "VR23") (pin "1") (pinfunction "CCW_1") (pintype "passive"))
    )
    (net (code "158") (name "Net-(VR24-CCW)") (class "Default")
      (node (ref "D47") (pin "C") (pinfunction "C_C") (pintype "passive"))
      (node (ref "D48") (pin "A") (pinfunction "A_A") (pintype "passive"))
      (node (ref "JP24") (pin "2") (pinfunction "2_2") (pintype "passive"))
      (node (ref "R44") (pin "1") (pinfunction "1_1") (pintype "passive"))
      (node (ref "VR24") (pin "1") (pinfunction "CCW_1") (pintype "passive"))
    )
    (net (code "159") (name "Net-(VR25-CCW)") (class "Default")
      (node (ref "R57") (pin "1") (pinfunction "1_1") (pintype "passive"))
      (node (ref "VR25") (pin "1") (pinfunction "CCW_1") (pintype "passive"))
    )
    (net (code "160") (name "REF") (class "Default")
      (node (ref "U1") (pin "10") (pinfunction "-IN_10") (pintype "input"))
      (node (ref "U1") (pin "4") (pinfunction "-IN_4") (pintype "input"))
      (node (ref "U1") (pin "6") (pinfunction "-IN_6") (pintype "input"))
      (node (ref "U1") (pin "8") (pinfunction "-IN_8") (pintype "input"))
      (node (ref "U2") (pin "10") (pinfunction "-IN_10") (pintype "input"))
      (node (ref "U2") (pin "4") (pinfunction "-IN_4") (pintype "input"))
      (node (ref "U2") (pin "6") (pinfunction "-IN_6") (pintype "input"))
      (node (ref "U2") (pin "8") (pinfunction "-IN_8") (pintype "input"))
      (node (ref "U3") (pin "10") (pinfunction "-IN_10") (pintype "input"))
      (node (ref "U3") (pin "4") (pinfunction "-IN_4") (pintype "input"))
      (node (ref "U3") (pin "6") (pinfunction "-IN_6") (pintype "input"))
      (node (ref "U3") (pin "8") (pinfunction "-IN_8") (pintype "input"))
      (node (ref "U4") (pin "10") (pinfunction "-IN_10") (pintype "input"))
      (node (ref "U4") (pin "4") (pinfunction "-IN_4") (pintype "input"))
      (node (ref "U4") (pin "6") (pinfunction "-IN_6") (pintype "input"))
      (node (ref "U4") (pin "8") (pinfunction "-IN_8") (pintype "input"))
      (node (ref "U5") (pin "10") (pinfunction "-IN_10") (pintype "input"))
      (node (ref "U5") (pin "4") (pinfunction "-IN_4") (pintype "input"))
      (node (ref "U5") (pin "6") (pinfunction "-IN_6") (pintype "input"))
      (node (ref "U5") (pin "8") (pinfunction "-IN_8") (pintype "input"))
      (node (ref "U6") (pin "10") (pinfunction "-IN_10") (pintype "input"))
      (node (ref "U6") (pin "4") (pinfunction "-IN_4") (pintype "input"))
      (node (ref "U6") (pin "6") (pinfunction "-IN_6") (pintype "input"))
      (node (ref "U6") (pin "8") (pinfunction "-IN_8") (pintype "input"))
      (node (ref "VR25") (pin "2") (pinfunction "WIPER_2") (pintype "passive"))
    )
    (net (code "161") (name "VCC") (class "Default")
      (node (ref "JP25") (pin "1") (pinfunction "1_1") (pintype "passive"))
      (node (ref "JP25") (pin "2") (pinfunction "2_2") (pintype "passive"))
      (node (ref "LED2") (pin "A") (pinfunction "A_A") (pintype "passive"))
      (node (ref "LED3") (pin "A") (pinfunction "A_A") (pintype "passive"))
      (node (ref "R56") (pin "1") (pinfunction "1_1") (pintype "passive"))
      (node (ref "U1") (pin "3") (pinfunction "VCC_3") (pintype "power_in"))
      (node (ref "U2") (pin "3") (pinfunction "VCC_3") (pintype "power_in"))
      (node (ref "U3") (pin "3") (pinfunction "VCC_3") (pintype "power_in"))
      (node (ref "U4") (pin "3") (pinfunction "VCC_3") (pintype "power_in"))
      (node (ref "U5") (pin "3") (pinfunction "VCC_3") (pintype "power_in"))
      (node (ref "U6") (pin "3") (pinfunction "VCC_3") (pintype "power_in"))
      (node (ref "U7") (pin "P$2") (pinfunction "MODE1_P$2") (pintype "bidirectional"))
      (node (ref "U7") (pin "P$5") (pinfunction "NSLEEP_P$5") (pintype "bidirectional"))
    )
    (net (code "162") (name "unconnected-(J1-Pad2)") (class "Default")
      (node (ref "J1") (pin "2") (pinfunction "2_2") (pintype "passive"))
    )
    (net (code "163") (name "unconnected-(JP26-Pad8)") (class "Default")
      (node (ref "JP26") (pin "8") (pinfunction "8_8") (pintype "passive"))
    )
  )
)
